# axiom_beta_sensor_cmv12000_v0_13.net
KiCad netlist of a schematic drawn in EAGLE
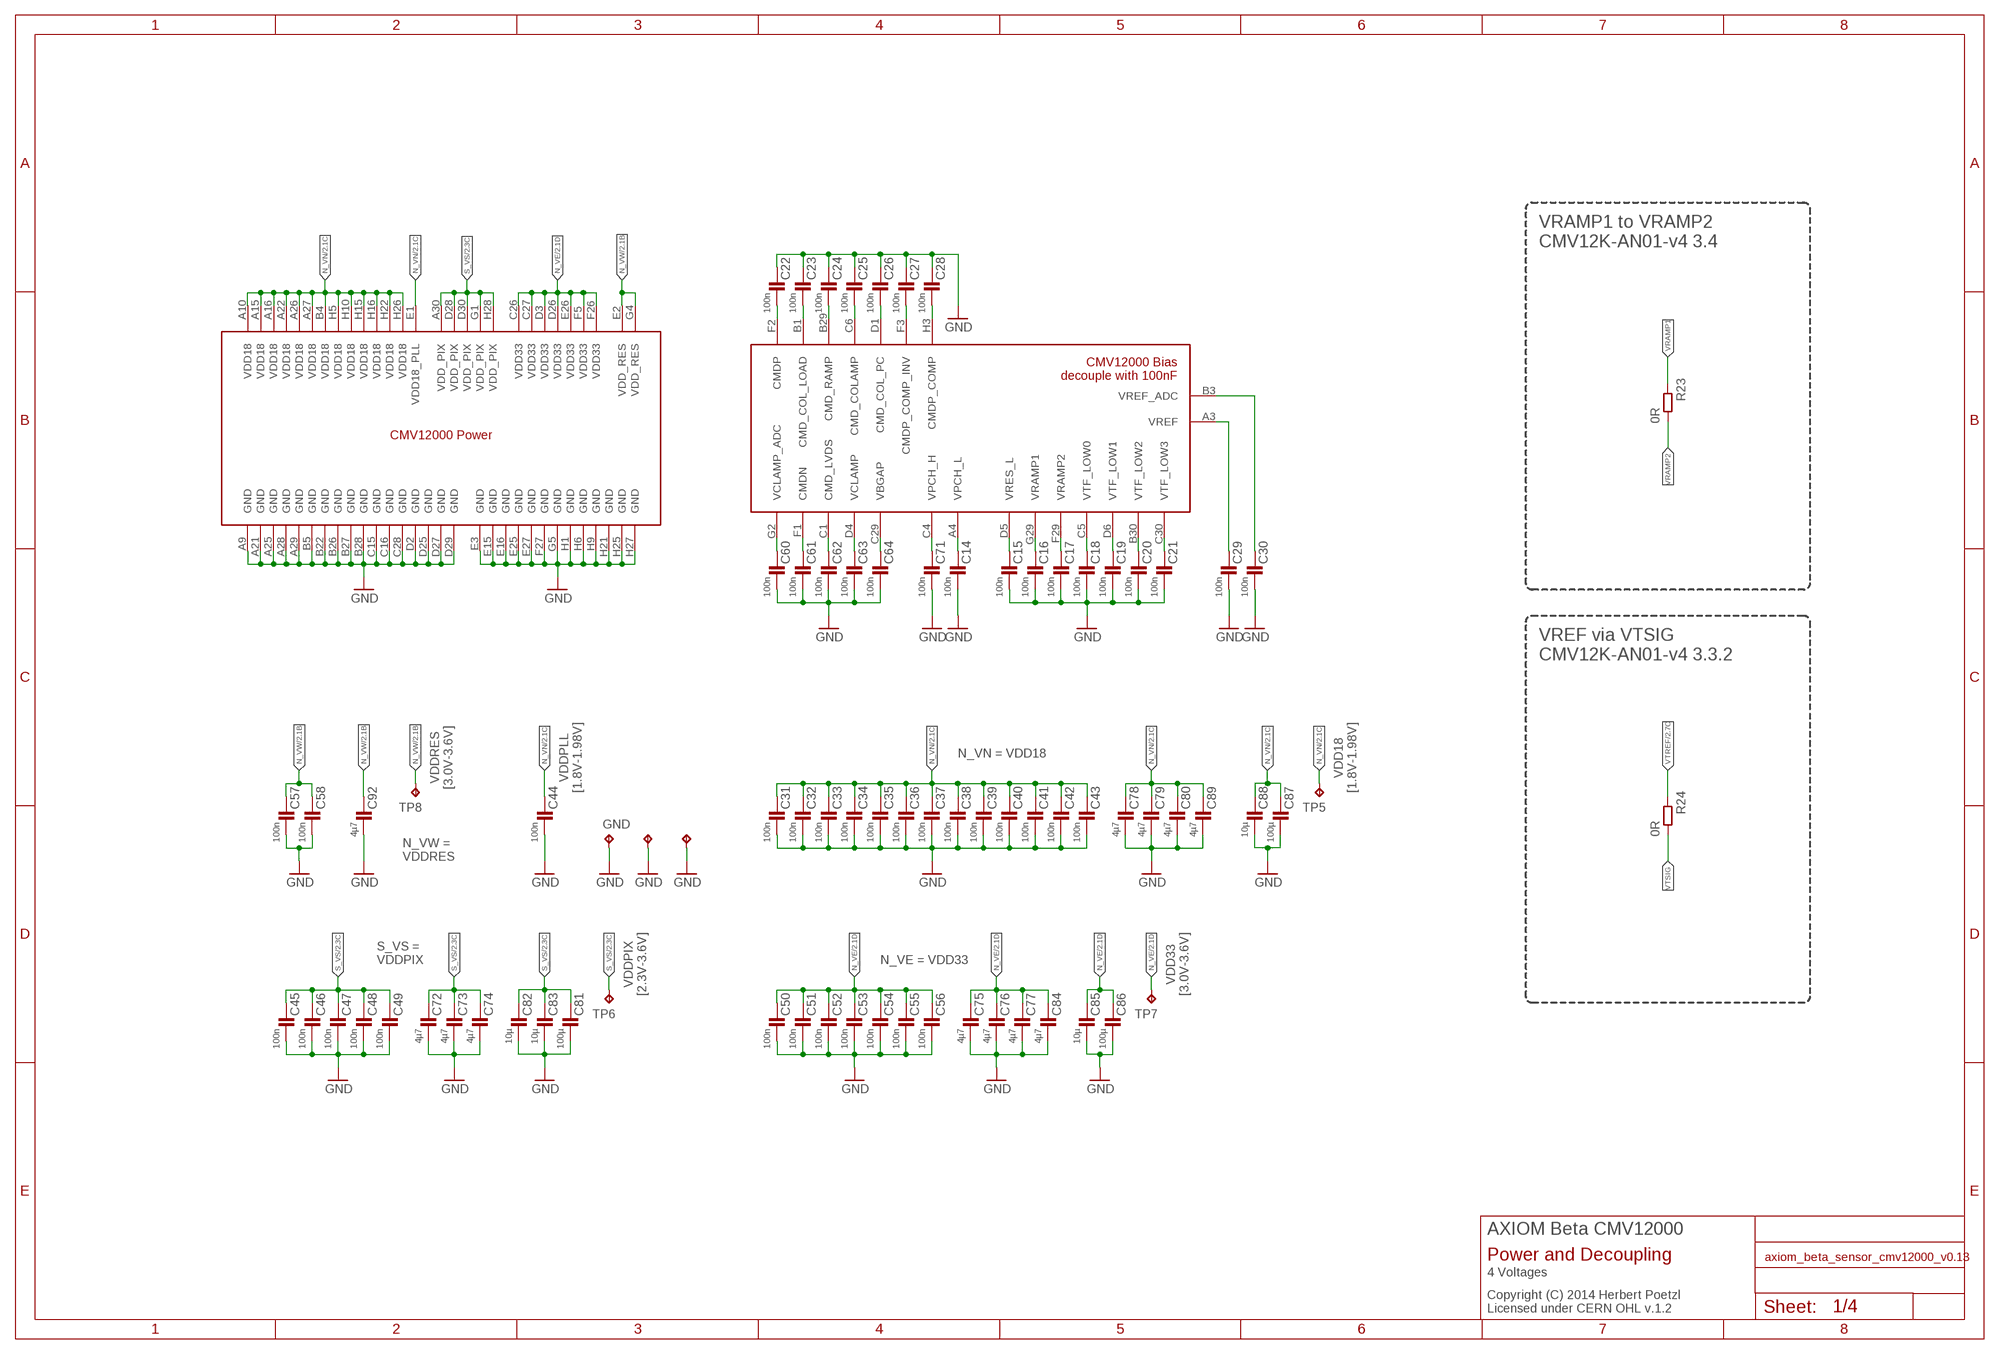
[diagram p0: schematic, sheet 1]
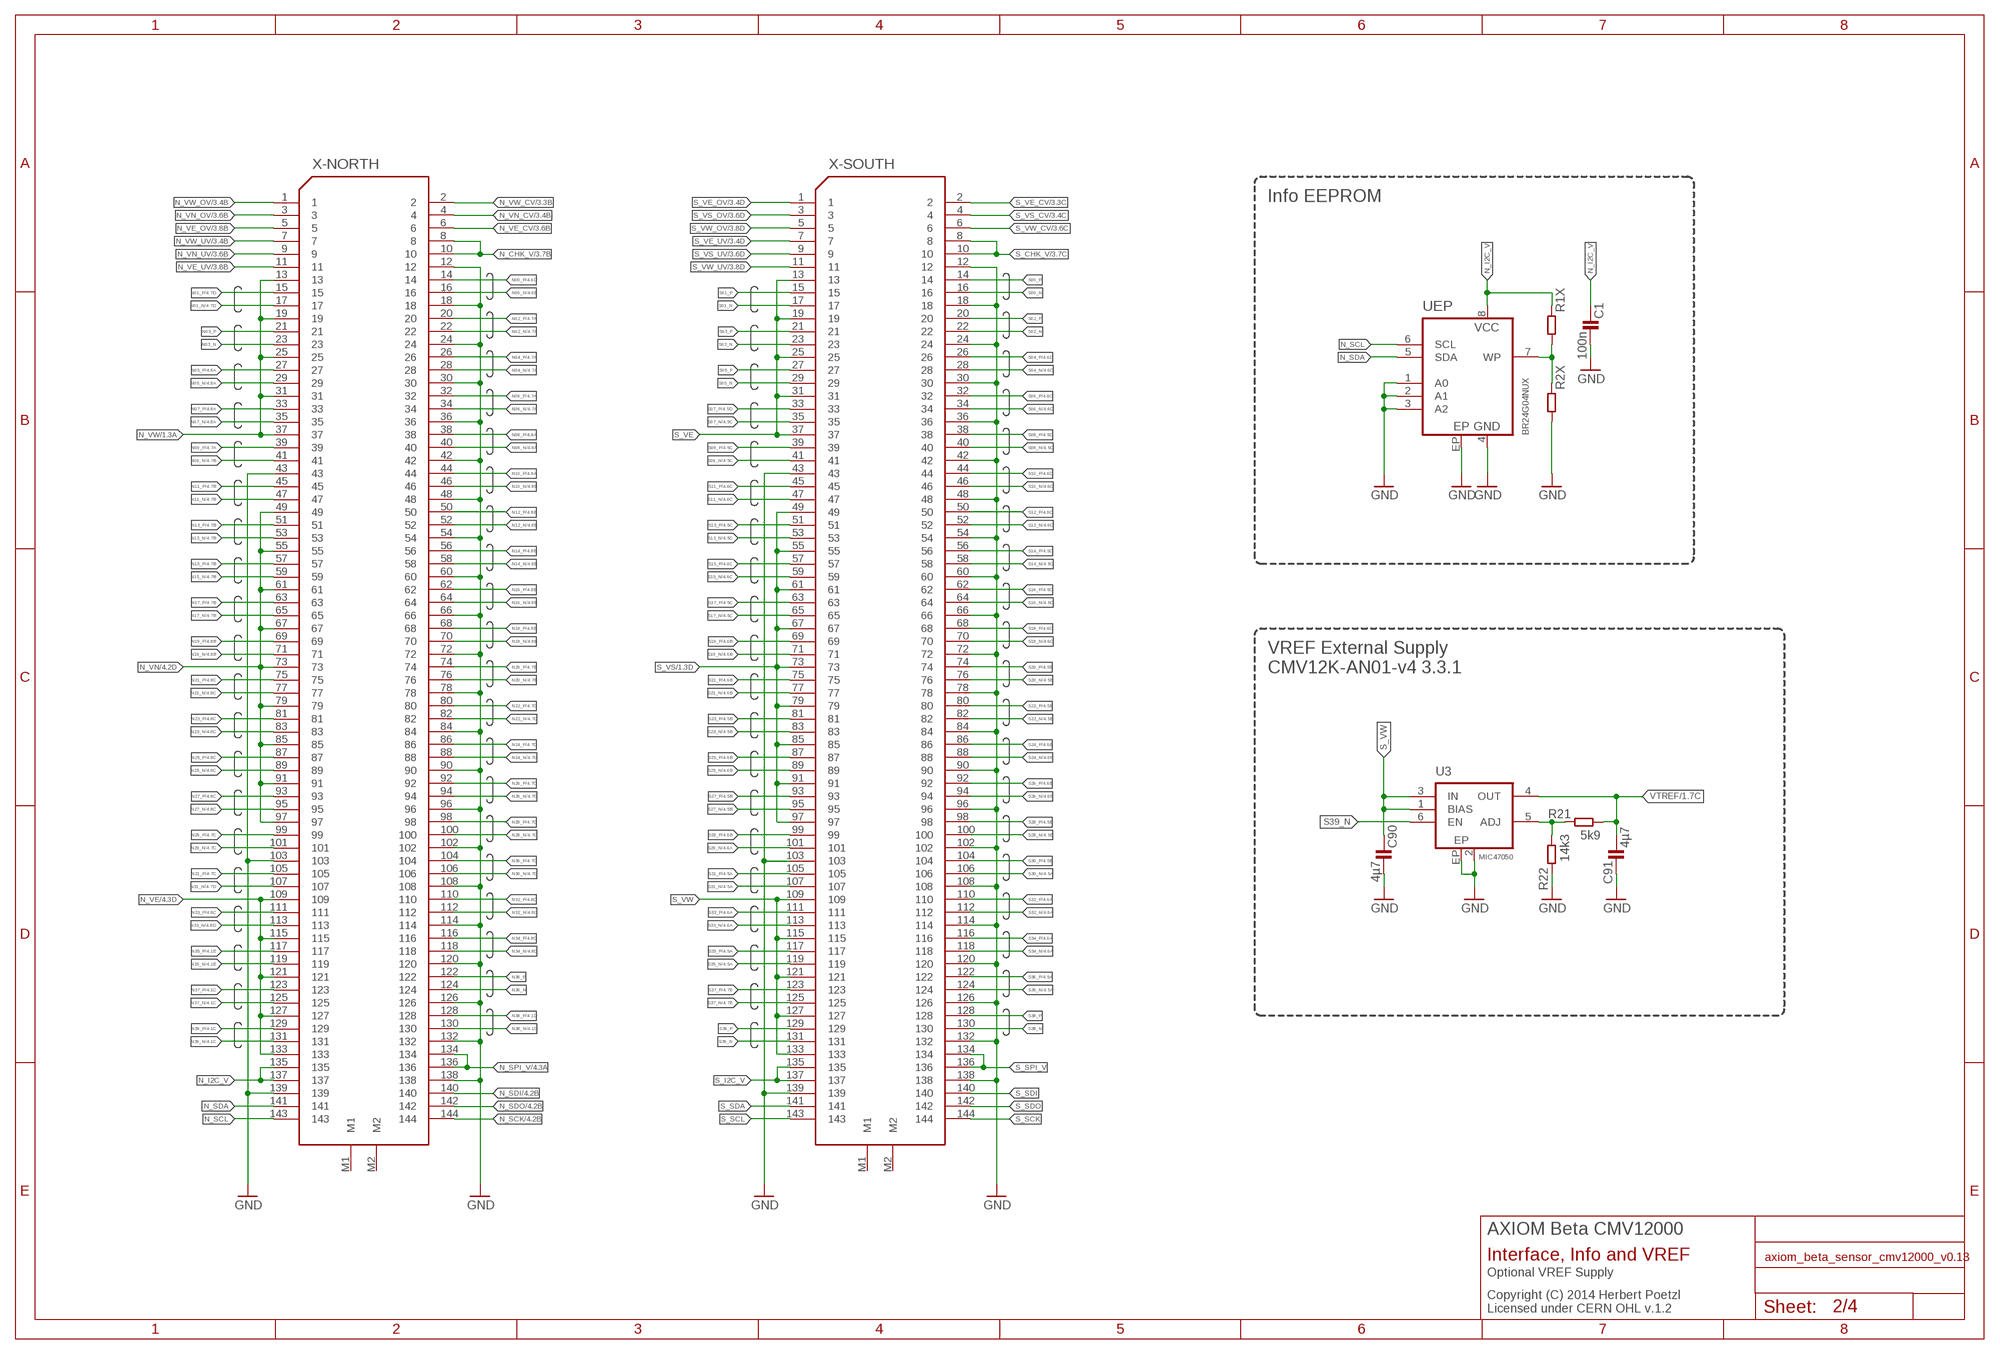
[diagram p1: schematic, sheet 2]
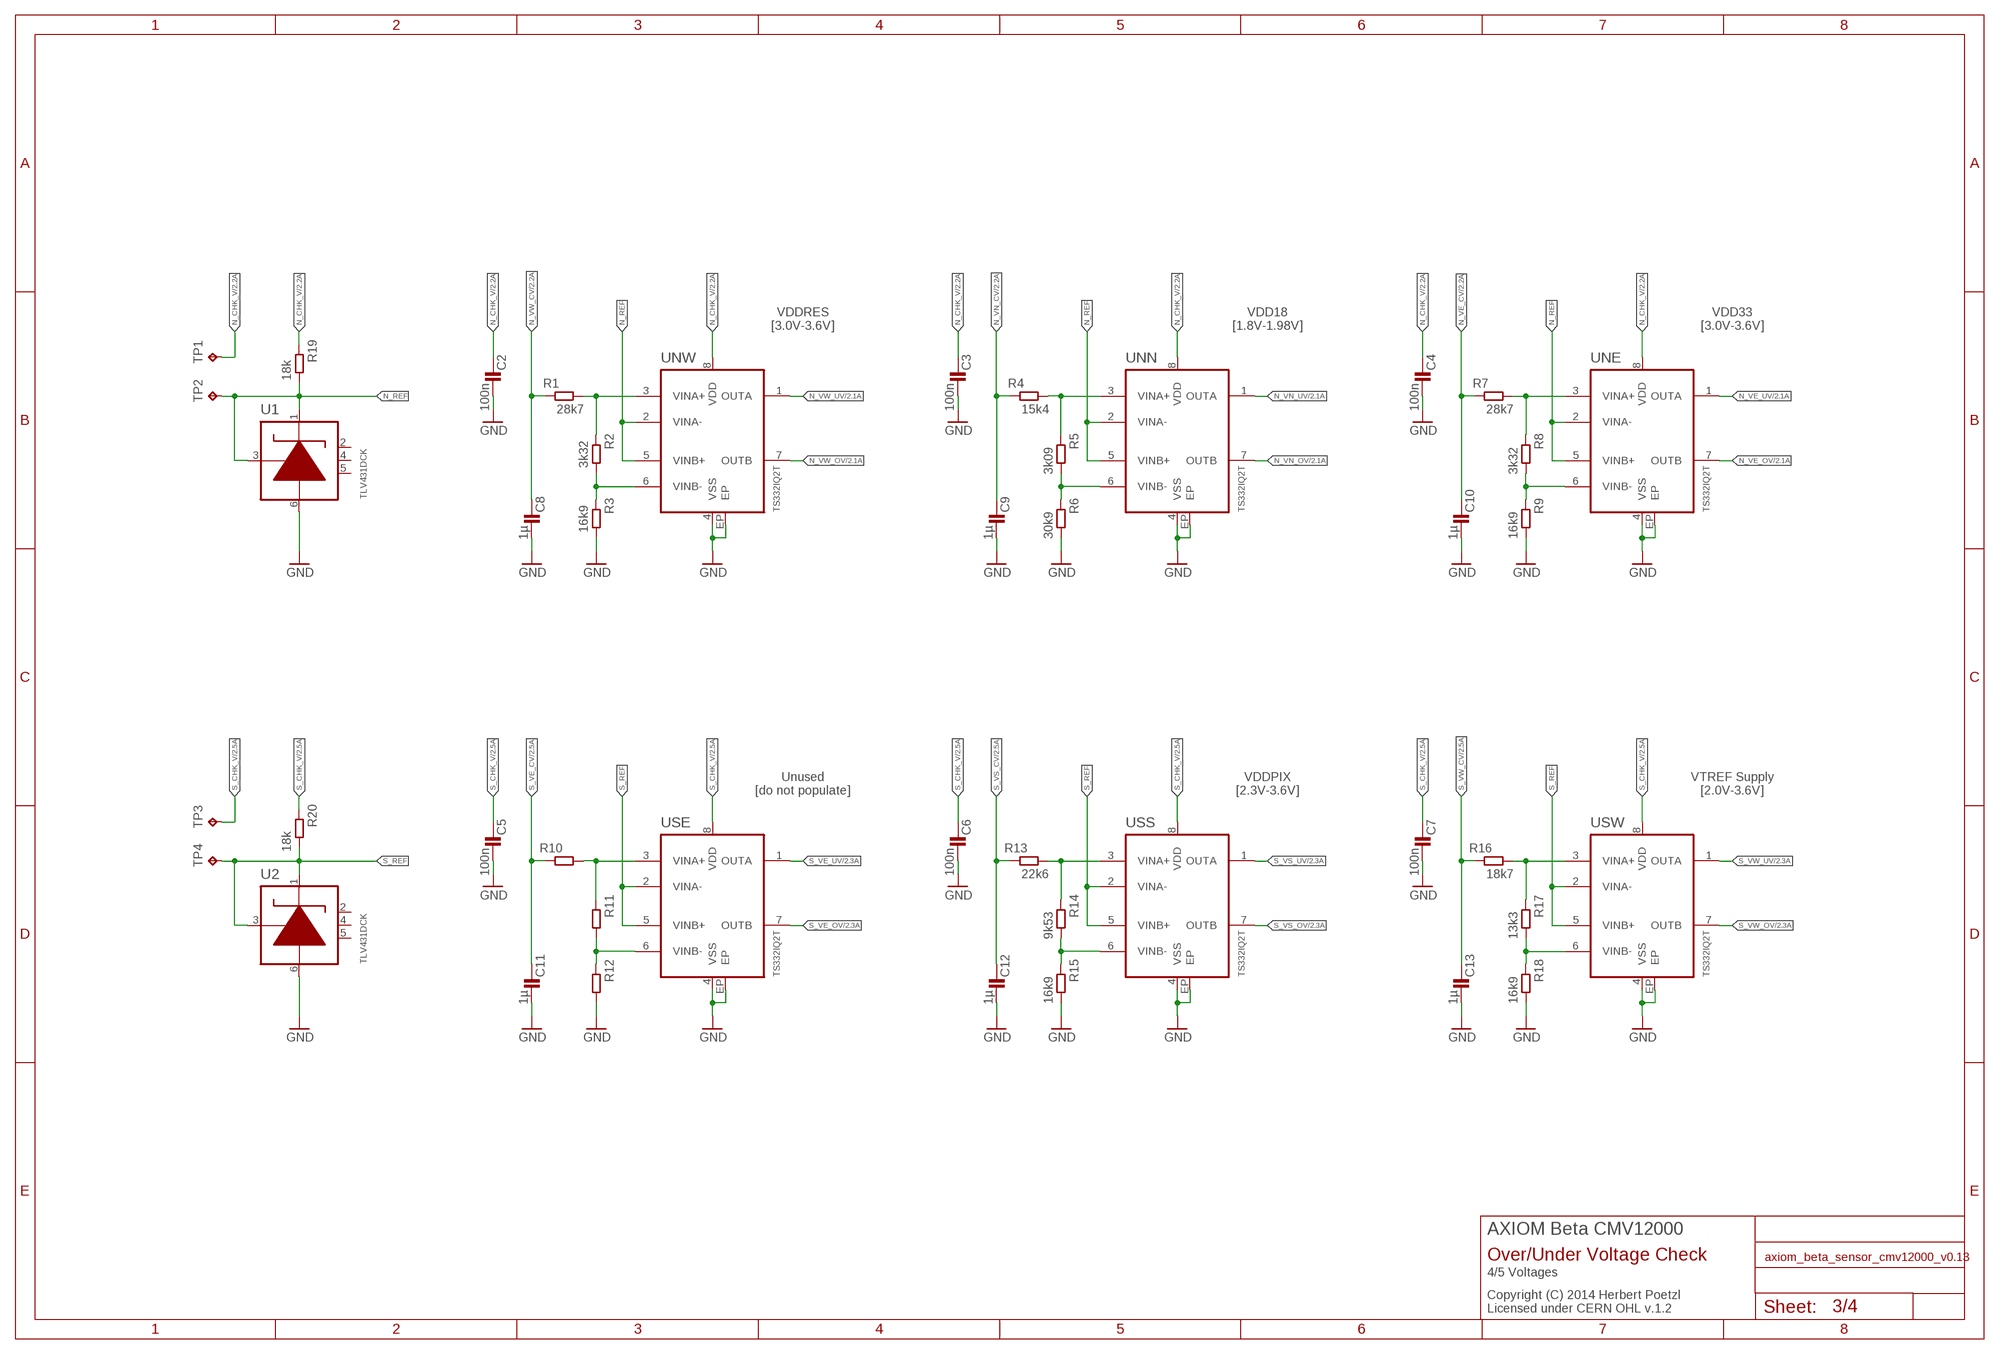
[diagram p2: schematic, sheet 3]
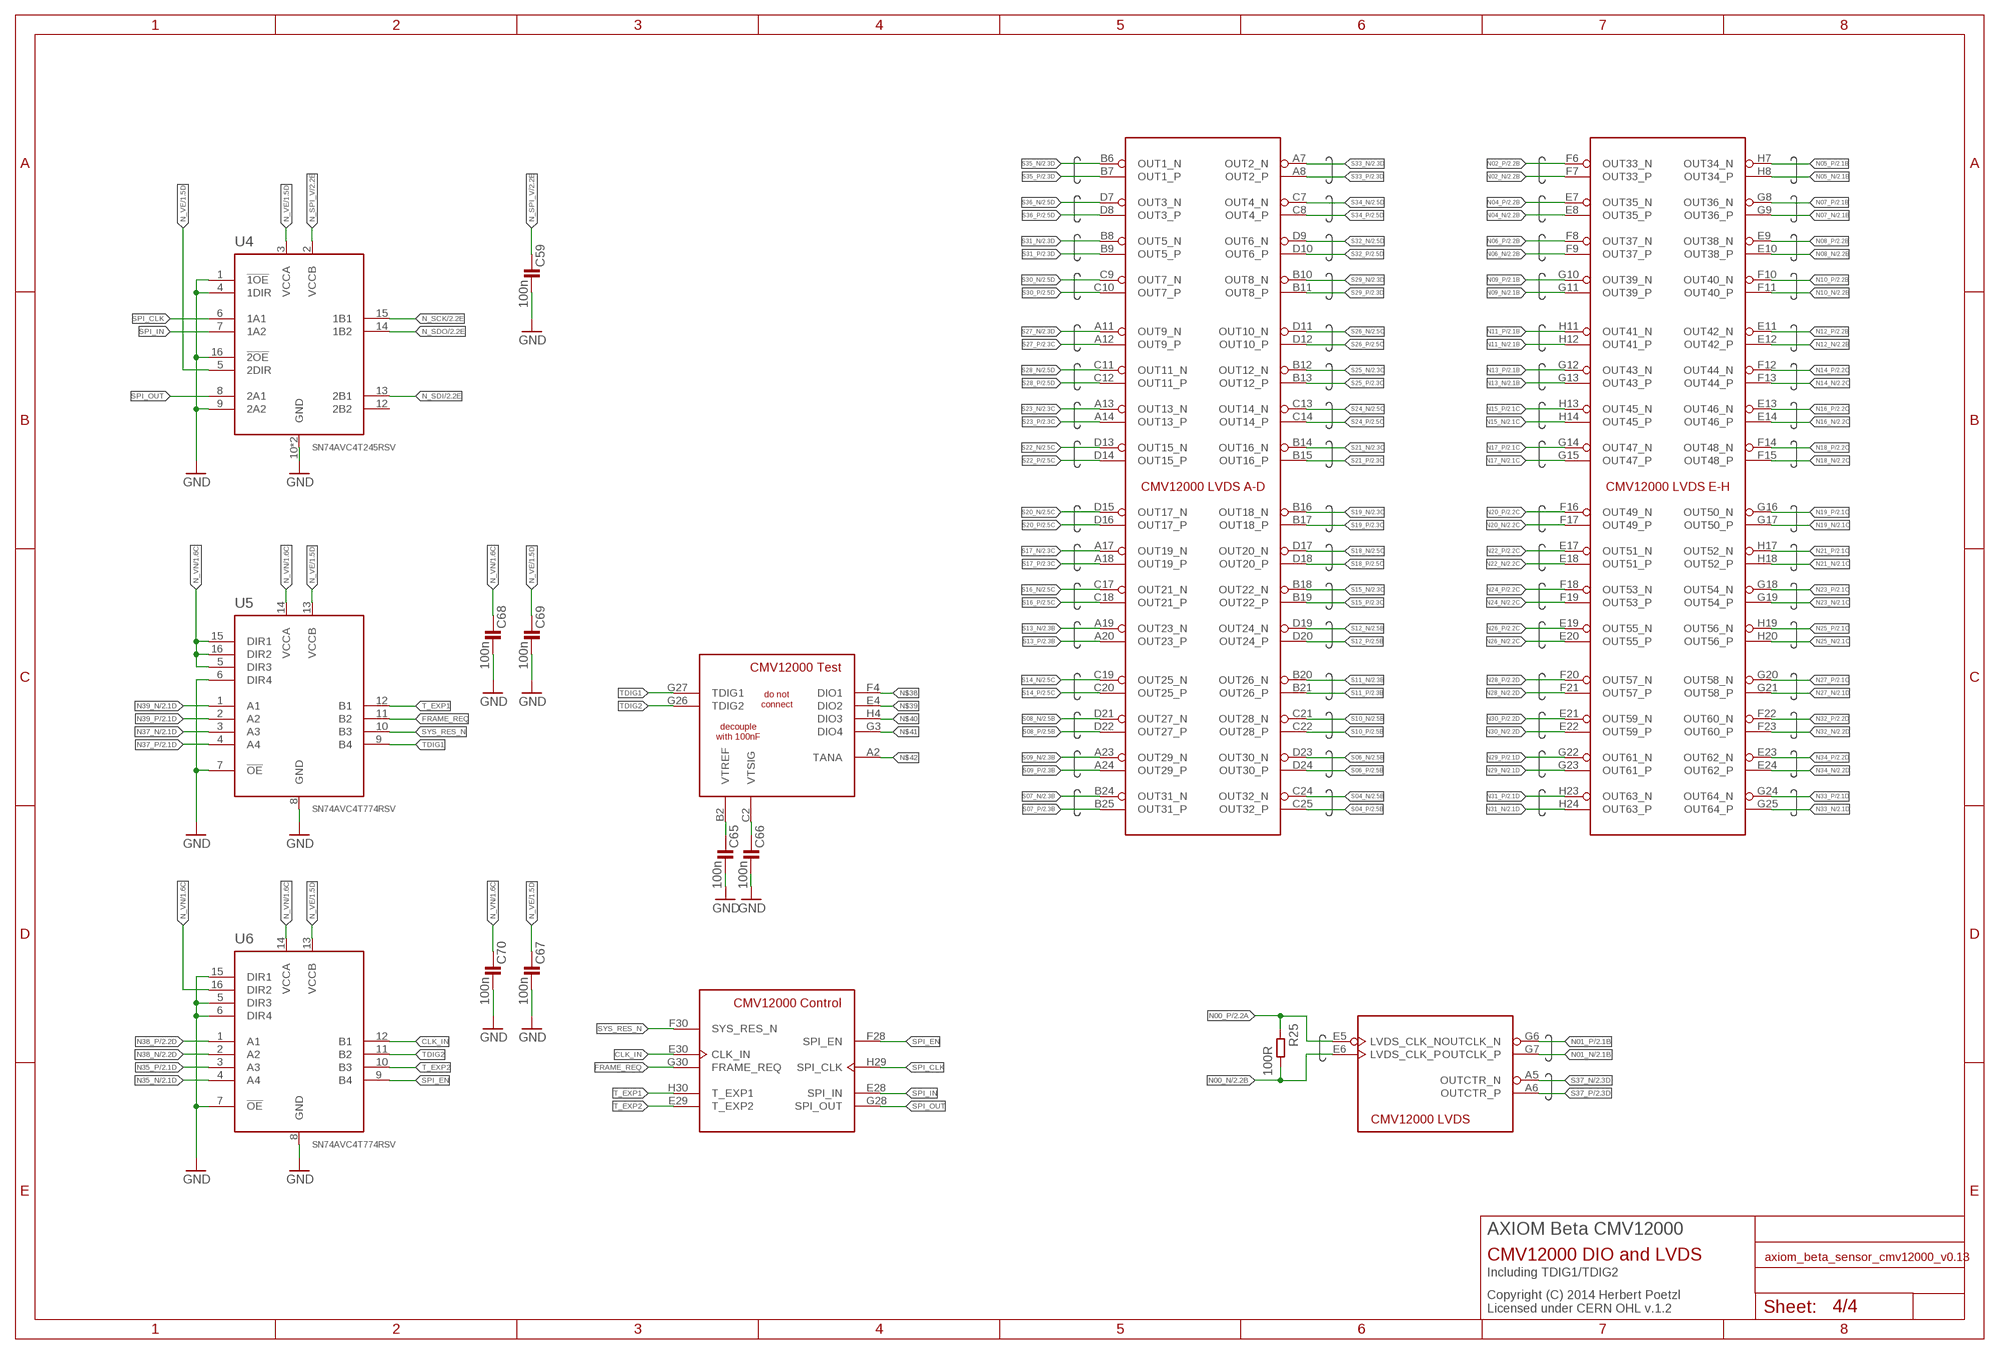
[diagram p3: schematic, sheet 4]

(export (version "E")
  (design (tool "Eeschema 10.0.6"))
  (components
    (comp (ref "C2")
      (value "100n")
      (footprint "eagle-import:0402-C")
      (libsource (lib "eagle-import") (part "C0402-C"))
    )
    (comp (ref "C3")
      (value "100n")
      (footprint "eagle-import:0402-C")
      (libsource (lib "eagle-import") (part "C0402-C"))
    )
    (comp (ref "C4")
      (value "100n")
      (footprint "eagle-import:0402-C")
      (libsource (lib "eagle-import") (part "C0402-C"))
    )
    (comp (ref "C5")
      (value "100n")
      (footprint "eagle-import:0402-C")
      (libsource (lib "eagle-import") (part "C0402-C"))
    )
    (comp (ref "C6")
      (value "100n")
      (footprint "eagle-import:0402-C")
      (libsource (lib "eagle-import") (part "C0402-C"))
    )
    (comp (ref "C7")
      (value "100n")
      (footprint "eagle-import:0402-C")
      (libsource (lib "eagle-import") (part "C0402-C"))
    )
    (comp (ref "C8")
      (value "1µ")
      (footprint "eagle-import:0402-C")
      (libsource (lib "eagle-import") (part "C0402-C"))
    )
    (comp (ref "C9")
      (value "1µ")
      (footprint "eagle-import:0402-C")
      (libsource (lib "eagle-import") (part "C0402-C"))
    )
    (comp (ref "C10")
      (value "1µ")
      (footprint "eagle-import:0402-C")
      (libsource (lib "eagle-import") (part "C0402-C"))
    )
    (comp (ref "C11")
      (value "1µ")
      (footprint "eagle-import:0402-C")
      (libsource (lib "eagle-import") (part "C0402-C"))
    )
    (comp (ref "C12")
      (value "1µ")
      (footprint "eagle-import:0402-C")
      (libsource (lib "eagle-import") (part "C0402-C"))
    )
    (comp (ref "C13")
      (value "1µ")
      (footprint "eagle-import:0402-C")
      (libsource (lib "eagle-import") (part "C0402-C"))
    )
    (comp (ref "R1")
      (value "28k7")
      (footprint "eagle-import:0402-C")
      (libsource (lib "eagle-import") (part "R0402-C"))
    )
    (comp (ref "R2")
      (value "3k32")
      (footprint "eagle-import:0402-C")
      (libsource (lib "eagle-import") (part "R0402-C"))
    )
    (comp (ref "R3")
      (value "16k9")
      (footprint "eagle-import:0402-C")
      (libsource (lib "eagle-import") (part "R0402-C"))
    )
    (comp (ref "R4")
      (value "15k4")
      (footprint "eagle-import:0402-C")
      (libsource (lib "eagle-import") (part "R0402-C"))
    )
    (comp (ref "R5")
      (value "3k09")
      (footprint "eagle-import:0402-C")
      (libsource (lib "eagle-import") (part "R0402-C"))
    )
    (comp (ref "R6")
      (value "30k9")
      (footprint "eagle-import:0402-C")
      (libsource (lib "eagle-import") (part "R0402-C"))
    )
    (comp (ref "R7")
      (value "28k7")
      (footprint "eagle-import:0402-C")
      (libsource (lib "eagle-import") (part "R0402-C"))
    )
    (comp (ref "R8")
      (value "3k32")
      (footprint "eagle-import:0402-C")
      (libsource (lib "eagle-import") (part "R0402-C"))
    )
    (comp (ref "R9")
      (value "16k9")
      (footprint "eagle-import:0402-C")
      (libsource (lib "eagle-import") (part "R0402-C"))
    )
    (comp (ref "R10")
      (value "R0402-C")
      (footprint "eagle-import:0402-C")
      (libsource (lib "eagle-import") (part "R0402-C"))
    )
    (comp (ref "R11")
      (value "R0402-C")
      (footprint "eagle-import:0402-C")
      (libsource (lib "eagle-import") (part "R0402-C"))
    )
    (comp (ref "R12")
      (value "R0402-C")
      (footprint "eagle-import:0402-C")
      (libsource (lib "eagle-import") (part "R0402-C"))
    )
    (comp (ref "R13")
      (value "22k6")
      (footprint "eagle-import:0402-C")
      (libsource (lib "eagle-import") (part "R0402-C"))
    )
    (comp (ref "R14")
      (value "9k53")
      (footprint "eagle-import:0402-C")
      (libsource (lib "eagle-import") (part "R0402-C"))
    )
    (comp (ref "R15")
      (value "16k9")
      (footprint "eagle-import:0402-C")
      (libsource (lib "eagle-import") (part "R0402-C"))
    )
    (comp (ref "R16")
      (value "18k7")
      (footprint "eagle-import:0402-C")
      (libsource (lib "eagle-import") (part "R0402-C"))
    )
    (comp (ref "R17")
      (value "13k3")
      (footprint "eagle-import:0402-C")
      (libsource (lib "eagle-import") (part "R0402-C"))
    )
    (comp (ref "R18")
      (value "16k9")
      (footprint "eagle-import:0402-C")
      (libsource (lib "eagle-import") (part "R0402-C"))
    )
    (comp (ref "R19")
      (value "18k")
      (footprint "eagle-import:0402-C")
      (libsource (lib "eagle-import") (part "R0402-C"))
    )
    (comp (ref "R20")
      (value "18k")
      (footprint "eagle-import:0402-C")
      (libsource (lib "eagle-import") (part "R0402-C"))
    )
    (comp (ref "TP1")
      (value "TPTP10R")
      (footprint "eagle-import:TP10R")
      (libsource (lib "eagle-import") (part "TPTP10R"))
    )
    (comp (ref "TP2")
      (value "TPTP10R")
      (footprint "eagle-import:TP10R")
      (libsource (lib "eagle-import") (part "TPTP10R"))
    )
    (comp (ref "TP3")
      (value "TPTP10R")
      (footprint "eagle-import:TP10R")
      (libsource (lib "eagle-import") (part "TPTP10R"))
    )
    (comp (ref "TP4")
      (value "TPTP10R")
      (footprint "eagle-import:TP10R")
      (libsource (lib "eagle-import") (part "TPTP10R"))
    )
    (comp (ref "U1")
      (value "TLV431DCK")
      (footprint "eagle-import:SOT65P210X110-6N")
      (libsource (lib "eagle-import") (part "TLV431DCK"))
    )
    (comp (ref "U2")
      (value "TLV431DCK")
      (footprint "eagle-import:SOT65P210X110-6N")
      (libsource (lib "eagle-import") (part "TLV431DCK"))
    )
    (comp (ref "UNE")
      (value "TS332IQ2T")
      (footprint "eagle-import:DFN200X200X100-9N")
      (libsource (lib "eagle-import") (part "TS332IQ2T"))
    )
    (comp (ref "UNN")
      (value "TS332IQ2T")
      (footprint "eagle-import:DFN200X200X100-9N")
      (libsource (lib "eagle-import") (part "TS332IQ2T"))
    )
    (comp (ref "UNW")
      (value "TS332IQ2T")
      (footprint "eagle-import:DFN200X200X100-9N")
      (libsource (lib "eagle-import") (part "TS332IQ2T"))
    )
    (comp (ref "USE")
      (value "TS332IQ2T")
      (footprint "eagle-import:DFN200X200X100-9N")
      (libsource (lib "eagle-import") (part "TS332IQ2T"))
    )
    (comp (ref "USS")
      (value "TS332IQ2T")
      (footprint "eagle-import:DFN200X200X100-9N")
      (libsource (lib "eagle-import") (part "TS332IQ2T"))
    )
    (comp (ref "USW")
      (value "TS332IQ2T")
      (footprint "eagle-import:DFN200X200X100-9N")
      (libsource (lib "eagle-import") (part "TS332IQ2T"))
    )
    (comp (ref "C1")
      (value "100n")
      (footprint "eagle-import:0402-C")
      (libsource (lib "eagle-import") (part "C0402-C"))
    )
    (comp (ref "C90")
      (value "4µ7")
      (footprint "eagle-import:0402-C")
      (libsource (lib "eagle-import") (part "C0402-C"))
    )
    (comp (ref "C91")
      (value "4µ7")
      (footprint "eagle-import:0402-C")
      (libsource (lib "eagle-import") (part "C0402-C"))
    )
    (comp (ref "R1X")
      (value "R0402-C")
      (footprint "eagle-import:0402-C")
      (libsource (lib "eagle-import") (part "R0402-C"))
    )
    (comp (ref "R2X")
      (value "R0402-C")
      (footprint "eagle-import:0402-C")
      (libsource (lib "eagle-import") (part "R0402-C"))
    )
    (comp (ref "R21")
      (value "5k9")
      (footprint "eagle-import:0402-C")
      (libsource (lib "eagle-import") (part "R0402-C"))
    )
    (comp (ref "R22")
      (value "14k3")
      (footprint "eagle-import:0402-C")
      (libsource (lib "eagle-import") (part "R0402-C"))
    )
    (comp (ref "U3")
      (value "MIC47050")
      (footprint "eagle-import:MLF-6")
      (libsource (lib "eagle-import") (part "MIC47050-ADJ"))
    )
    (comp (ref "UEP")
      (value "BR24G04NUX")
      (footprint "eagle-import:DFN200X300X100-9N")
      (libsource (lib "eagle-import") (part "BR24G04NUX"))
    )
    (comp (ref "X-NORTH")
      (value "FX10-144P")
      (footprint "eagle-import:FX10A-144P")
      (libsource (lib "eagle-import") (part "FX10-144P"))
    )
    (comp (ref "X-SOUTH")
      (value "FX10-144P")
      (footprint "eagle-import:FX10A-144P")
      (libsource (lib "eagle-import") (part "FX10-144P"))
    )
    (comp (ref "C14")
      (value "100n")
      (footprint "eagle-import:0402-C")
      (libsource (lib "eagle-import") (part "C0402-C"))
    )
    (comp (ref "C15")
      (value "100n")
      (footprint "eagle-import:0402-C")
      (libsource (lib "eagle-import") (part "C0402-C"))
    )
    (comp (ref "C16")
      (value "100n")
      (footprint "eagle-import:0402-C")
      (libsource (lib "eagle-import") (part "C0402-C"))
    )
    (comp (ref "C17")
      (value "100n")
      (footprint "eagle-import:0402-C")
      (libsource (lib "eagle-import") (part "C0402-C"))
    )
    (comp (ref "C18")
      (value "100n")
      (footprint "eagle-import:0402-C")
      (libsource (lib "eagle-import") (part "C0402-C"))
    )
    (comp (ref "C19")
      (value "100n")
      (footprint "eagle-import:0402-C")
      (libsource (lib "eagle-import") (part "C0402-C"))
    )
    (comp (ref "C20")
      (value "100n")
      (footprint "eagle-import:0402-C")
      (libsource (lib "eagle-import") (part "C0402-C"))
    )
    (comp (ref "C21")
      (value "100n")
      (footprint "eagle-import:0402-C")
      (libsource (lib "eagle-import") (part "C0402-C"))
    )
    (comp (ref "C22")
      (value "100n")
      (footprint "eagle-import:0402-C")
      (libsource (lib "eagle-import") (part "C0402-C"))
    )
    (comp (ref "C23")
      (value "100n")
      (footprint "eagle-import:0402-C")
      (libsource (lib "eagle-import") (part "C0402-C"))
    )
    (comp (ref "C24")
      (value "100n")
      (footprint "eagle-import:0402-C")
      (libsource (lib "eagle-import") (part "C0402-C"))
    )
    (comp (ref "C25")
      (value "100n")
      (footprint "eagle-import:0402-C")
      (libsource (lib "eagle-import") (part "C0402-C"))
    )
    (comp (ref "C26")
      (value "100n")
      (footprint "eagle-import:0402-C")
      (libsource (lib "eagle-import") (part "C0402-C"))
    )
    (comp (ref "C27")
      (value "100n")
      (footprint "eagle-import:0402-C")
      (libsource (lib "eagle-import") (part "C0402-C"))
    )
    (comp (ref "C28")
      (value "100n")
      (footprint "eagle-import:0402-C")
      (libsource (lib "eagle-import") (part "C0402-C"))
    )
    (comp (ref "C29")
      (value "100n")
      (footprint "eagle-import:0402-C")
      (libsource (lib "eagle-import") (part "C0402-C"))
    )
    (comp (ref "C30")
      (value "100n")
      (footprint "eagle-import:0402-C")
      (libsource (lib "eagle-import") (part "C0402-C"))
    )
    (comp (ref "C31")
      (value "100n")
      (footprint "eagle-import:0402-C")
      (libsource (lib "eagle-import") (part "C0402-C"))
    )
    (comp (ref "C32")
      (value "100n")
      (footprint "eagle-import:0402-C")
      (libsource (lib "eagle-import") (part "C0402-C"))
    )
    (comp (ref "C33")
      (value "100n")
      (footprint "eagle-import:0402-C")
      (libsource (lib "eagle-import") (part "C0402-C"))
    )
    (comp (ref "C34")
      (value "100n")
      (footprint "eagle-import:0402-C")
      (libsource (lib "eagle-import") (part "C0402-C"))
    )
    (comp (ref "C35")
      (value "100n")
      (footprint "eagle-import:0402-C")
      (libsource (lib "eagle-import") (part "C0402-C"))
    )
    (comp (ref "C36")
      (value "100n")
      (footprint "eagle-import:0402-C")
      (libsource (lib "eagle-import") (part "C0402-C"))
    )
    (comp (ref "C37")
      (value "100n")
      (footprint "eagle-import:0402-C")
      (libsource (lib "eagle-import") (part "C0402-C"))
    )
    (comp (ref "C38")
      (value "100n")
      (footprint "eagle-import:0402-C")
      (libsource (lib "eagle-import") (part "C0402-C"))
    )
    (comp (ref "C39")
      (value "100n")
      (footprint "eagle-import:0402-C")
      (libsource (lib "eagle-import") (part "C0402-C"))
    )
    (comp (ref "C40")
      (value "100n")
      (footprint "eagle-import:0402-C")
      (libsource (lib "eagle-import") (part "C0402-C"))
    )
    (comp (ref "C41")
      (value "100n")
      (footprint "eagle-import:0402-C")
      (libsource (lib "eagle-import") (part "C0402-C"))
    )
    (comp (ref "C42")
      (value "100n")
      (footprint "eagle-import:0402-C")
      (libsource (lib "eagle-import") (part "C0402-C"))
    )
    (comp (ref "C43")
      (value "100n")
      (footprint "eagle-import:0402-C")
      (libsource (lib "eagle-import") (part "C0402-C"))
    )
    (comp (ref "C44")
      (value "100n")
      (footprint "eagle-import:0402-C")
      (libsource (lib "eagle-import") (part "C0402-C"))
    )
    (comp (ref "C45")
      (value "100n")
      (footprint "eagle-import:0402-C")
      (libsource (lib "eagle-import") (part "C0402-C"))
    )
    (comp (ref "C46")
      (value "100n")
      (footprint "eagle-import:0402-C")
      (libsource (lib "eagle-import") (part "C0402-C"))
    )
    (comp (ref "C47")
      (value "100n")
      (footprint "eagle-import:0402-C")
      (libsource (lib "eagle-import") (part "C0402-C"))
    )
    (comp (ref "C48")
      (value "100n")
      (footprint "eagle-import:0402-C")
      (libsource (lib "eagle-import") (part "C0402-C"))
    )
    (comp (ref "C49")
      (value "100n")
      (footprint "eagle-import:0402-C")
      (libsource (lib "eagle-import") (part "C0402-C"))
    )
    (comp (ref "C50")
      (value "100n")
      (footprint "eagle-import:0402-C")
      (libsource (lib "eagle-import") (part "C0402-C"))
    )
    (comp (ref "C51")
      (value "100n")
      (footprint "eagle-import:0402-C")
      (libsource (lib "eagle-import") (part "C0402-C"))
    )
    (comp (ref "C52")
      (value "100n")
      (footprint "eagle-import:0402-C")
      (libsource (lib "eagle-import") (part "C0402-C"))
    )
    (comp (ref "C53")
      (value "100n")
      (footprint "eagle-import:0402-C")
      (libsource (lib "eagle-import") (part "C0402-C"))
    )
    (comp (ref "C54")
      (value "100n")
      (footprint "eagle-import:0402-C")
      (libsource (lib "eagle-import") (part "C0402-C"))
    )
    (comp (ref "C55")
      (value "100n")
      (footprint "eagle-import:0402-C")
      (libsource (lib "eagle-import") (part "C0402-C"))
    )
    (comp (ref "C56")
      (value "100n")
      (footprint "eagle-import:0402-C")
      (libsource (lib "eagle-import") (part "C0402-C"))
    )
    (comp (ref "C57")
      (value "100n")
      (footprint "eagle-import:0402-C")
      (libsource (lib "eagle-import") (part "C0402-C"))
    )
    (comp (ref "C58")
      (value "100n")
      (footprint "eagle-import:0402-C")
      (libsource (lib "eagle-import") (part "C0402-C"))
    )
    (comp (ref "C60")
      (value "100n")
      (footprint "eagle-import:0402-C")
      (libsource (lib "eagle-import") (part "C0402-C"))
    )
    (comp (ref "C61")
      (value "100n")
      (footprint "eagle-import:0402-C")
      (libsource (lib "eagle-import") (part "C0402-C"))
    )
    (comp (ref "C62")
      (value "100n")
      (footprint "eagle-import:0402-C")
      (libsource (lib "eagle-import") (part "C0402-C"))
    )
    (comp (ref "C63")
      (value "100n")
      (footprint "eagle-import:0402-C")
      (libsource (lib "eagle-import") (part "C0402-C"))
    )
    (comp (ref "C64")
      (value "100n")
      (footprint "eagle-import:0402-C")
      (libsource (lib "eagle-import") (part "C0402-C"))
    )
    (comp (ref "C71")
      (value "100n")
      (footprint "eagle-import:0402-C")
      (libsource (lib "eagle-import") (part "C0402-C"))
    )
    (comp (ref "C72")
      (value "4µ7")
      (footprint "eagle-import:0402-B")
      (libsource (lib "eagle-import") (part "C0402-B"))
    )
    (comp (ref "C73")
      (value "4µ7")
      (footprint "eagle-import:0402-C")
      (libsource (lib "eagle-import") (part "C0402-C"))
    )
    (comp (ref "C74")
      (value "4µ7")
      (footprint "eagle-import:0402-C")
      (libsource (lib "eagle-import") (part "C0402-C"))
    )
    (comp (ref "C75")
      (value "4µ7")
      (footprint "eagle-import:0402-C")
      (libsource (lib "eagle-import") (part "C0402-C"))
    )
    (comp (ref "C76")
      (value "4µ7")
      (footprint "eagle-import:0402-C")
      (libsource (lib "eagle-import") (part "C0402-C"))
    )
    (comp (ref "C77")
      (value "4µ7")
      (footprint "eagle-import:0402-B")
      (libsource (lib "eagle-import") (part "C0402-B"))
    )
    (comp (ref "C78")
      (value "4µ7")
      (footprint "eagle-import:0402-B")
      (libsource (lib "eagle-import") (part "C0402-B"))
    )
    (comp (ref "C79")
      (value "4µ7")
      (footprint "eagle-import:0402-C")
      (libsource (lib "eagle-import") (part "C0402-C"))
    )
    (comp (ref "C80")
      (value "4µ7")
      (footprint "eagle-import:0402-C")
      (libsource (lib "eagle-import") (part "C0402-C"))
    )
    (comp (ref "C81")
      (value "100µ")
      (footprint "eagle-import:1206-B")
      (libsource (lib "eagle-import") (part "C1206-B"))
    )
    (comp (ref "C82")
      (value "10µ")
      (footprint "eagle-import:0603-C")
      (libsource (lib "eagle-import") (part "C0603-C"))
    )
    (comp (ref "C83")
      (value "10µ")
      (footprint "eagle-import:0603-C")
      (libsource (lib "eagle-import") (part "C0603-C"))
    )
    (comp (ref "C84")
      (value "4µ7")
      (footprint "eagle-import:0402-C")
      (libsource (lib "eagle-import") (part "C0402-C"))
    )
    (comp (ref "C85")
      (value "10µ")
      (footprint "eagle-import:0603-C")
      (libsource (lib "eagle-import") (part "C0603-C"))
    )
    (comp (ref "C86")
      (value "100µ")
      (footprint "eagle-import:1206-B")
      (libsource (lib "eagle-import") (part "C1206-B"))
    )
    (comp (ref "C87")
      (value "100µ")
      (footprint "eagle-import:1206-B")
      (libsource (lib "eagle-import") (part "C1206-B"))
    )
    (comp (ref "C88")
      (value "10µ")
      (footprint "eagle-import:0603-C")
      (libsource (lib "eagle-import") (part "C0603-C"))
    )
    (comp (ref "C89")
      (value "4µ7")
      (footprint "eagle-import:0402-C")
      (libsource (lib "eagle-import") (part "C0402-C"))
    )
    (comp (ref "C92")
      (value "4µ7")
      (footprint "eagle-import:0402-C")
      (libsource (lib "eagle-import") (part "C0402-C"))
    )
    (comp (ref "GND")
      (value "TPTP10R")
      (footprint "eagle-import:TP10R")
      (libsource (lib "eagle-import") (part "TPTP10R"))
    )
    (comp (ref "GND75")
      (value "TPTP10R")
      (footprint "eagle-import:TP10R")
      (libsource (lib "eagle-import") (part "TPTP10R"))
    )
    (comp (ref "GND77")
      (value "TPTP10R")
      (footprint "eagle-import:TP10R")
      (libsource (lib "eagle-import") (part "TPTP10R"))
    )
    (comp (ref "R23")
      (value "0R")
      (footprint "eagle-import:0402-C")
      (libsource (lib "eagle-import") (part "R0402-C"))
    )
    (comp (ref "R24")
      (value "0R")
      (footprint "eagle-import:0402-C")
      (libsource (lib "eagle-import") (part "R0402-C"))
    )
    (comp (ref "SENSOR")
      (value "CMV12000ANDON")
      (footprint "eagle-import:10-30-07-237-400T4")
      (libsource (lib "eagle-import") (part "CMV12000ANDON"))
    )
    (comp (ref "TP5")
      (value "TPTP10R")
      (footprint "eagle-import:TP10R")
      (libsource (lib "eagle-import") (part "TPTP10R"))
    )
    (comp (ref "TP6")
      (value "TPTP10R")
      (footprint "eagle-import:TP10R")
      (libsource (lib "eagle-import") (part "TPTP10R"))
    )
    (comp (ref "TP7")
      (value "TPTP10R")
      (footprint "eagle-import:TP10R")
      (libsource (lib "eagle-import") (part "TPTP10R"))
    )
    (comp (ref "TP8")
      (value "TPTP10R")
      (footprint "eagle-import:TP10R")
      (libsource (lib "eagle-import") (part "TPTP10R"))
    )
    (comp (ref "C59")
      (value "100n")
      (footprint "eagle-import:0402-C")
      (libsource (lib "eagle-import") (part "C0402-C"))
    )
    (comp (ref "C65")
      (value "100n")
      (footprint "eagle-import:0402-C")
      (libsource (lib "eagle-import") (part "C0402-C"))
    )
    (comp (ref "C66")
      (value "100n")
      (footprint "eagle-import:0402-C")
      (libsource (lib "eagle-import") (part "C0402-C"))
    )
    (comp (ref "C67")
      (value "100n")
      (footprint "eagle-import:0402-C")
      (libsource (lib "eagle-import") (part "C0402-C"))
    )
    (comp (ref "C68")
      (value "100n")
      (footprint "eagle-import:0402-C")
      (libsource (lib "eagle-import") (part "C0402-C"))
    )
    (comp (ref "C69")
      (value "100n")
      (footprint "eagle-import:0402-C")
      (libsource (lib "eagle-import") (part "C0402-C"))
    )
    (comp (ref "C70")
      (value "100n")
      (footprint "eagle-import:0402-C")
      (libsource (lib "eagle-import") (part "C0402-C"))
    )
    (comp (ref "R25")
      (value "100R")
      (footprint "eagle-import:0402-C")
      (libsource (lib "eagle-import") (part "R0402-C"))
    )
    (comp (ref "U4")
      (value "SN74AVC4T245RSV")
      (footprint "eagle-import:QFN40P185X265X55-16N")
      (libsource (lib "eagle-import") (part "SN74AVC4T245RSV"))
    )
    (comp (ref "U5")
      (value "SN74AVC4T774RSV")
      (footprint "eagle-import:QFN40P185X265X55-16N")
      (libsource (lib "eagle-import") (part "SN74AVC4T774RSV"))
    )
    (comp (ref "U6")
      (value "SN74AVC4T774RSV")
      (footprint "eagle-import:QFN40P185X265X55-16N")
      (libsource (lib "eagle-import") (part "SN74AVC4T774RSV"))
    )
  )
  (nets
    (net (code "1") (name "CLK_IN") (class "Default")
      (node (ref "SENSOR") (pin "E30") (pinfunction "CLK_IN_E30") (pintype "input"))
      (node (ref "U6") (pin "12") (pinfunction "B1_12") (pintype "bidirectional"))
    )
    (net (code "2") (name "FRAME_REQ") (class "Default")
      (node (ref "SENSOR") (pin "G30") (pinfunction "FRAME_REQ_G30") (pintype "input"))
      (node (ref "U5") (pin "11") (pinfunction "B2_11") (pintype "bidirectional"))
    )
    (net (code "3") (name "GND") (class "Default")
      (node (ref "C1") (pin "2") (pinfunction "2_2") (pintype "passive"))
      (node (ref "C10") (pin "2") (pinfunction "2_2") (pintype "passive"))
      (node (ref "C11") (pin "2") (pinfunction "2_2") (pintype "passive"))
      (node (ref "C12") (pin "2") (pinfunction "2_2") (pintype "passive"))
      (node (ref "C13") (pin "2") (pinfunction "2_2") (pintype "passive"))
      (node (ref "C14") (pin "2") (pinfunction "2_2") (pintype "passive"))
      (node (ref "C15") (pin "2") (pinfunction "2_2") (pintype "passive"))
      (node (ref "C16") (pin "2") (pinfunction "2_2") (pintype "passive"))
      (node (ref "C17") (pin "2") (pinfunction "2_2") (pintype "passive"))
      (node (ref "C18") (pin "2") (pinfunction "2_2") (pintype "passive"))
      (node (ref "C19") (pin "2") (pinfunction "2_2") (pintype "passive"))
      (node (ref "C2") (pin "2") (pinfunction "2_2") (pintype "passive"))
      (node (ref "C20") (pin "2") (pinfunction "2_2") (pintype "passive"))
      (node (ref "C21") (pin "2") (pinfunction "2_2") (pintype "passive"))
      (node (ref "C22") (pin "1") (pinfunction "1_1") (pintype "passive"))
      (node (ref "C23") (pin "1") (pinfunction "1_1") (pintype "passive"))
      (node (ref "C24") (pin "1") (pinfunction "1_1") (pintype "passive"))
      (node (ref "C25") (pin "1") (pinfunction "1_1") (pintype "passive"))
      (node (ref "C26") (pin "1") (pinfunction "1_1") (pintype "passive"))
      (node (ref "C27") (pin "1") (pinfunction "1_1") (pintype "passive"))
      (node (ref "C28") (pin "1") (pinfunction "1_1") (pintype "passive"))
      (node (ref "C29") (pin "2") (pinfunction "2_2") (pintype "passive"))
      (node (ref "C3") (pin "2") (pinfunction "2_2") (pintype "passive"))
      (node (ref "C30") (pin "2") (pinfunction "2_2") (pintype "passive"))
      (node (ref "C31") (pin "2") (pinfunction "2_2") (pintype "passive"))
      (node (ref "C32") (pin "2") (pinfunction "2_2") (pintype "passive"))
      (node (ref "C33") (pin "2") (pinfunction "2_2") (pintype "passive"))
      (node (ref "C34") (pin "2") (pinfunction "2_2") (pintype "passive"))
      (node (ref "C35") (pin "2") (pinfunction "2_2") (pintype "passive"))
      (node (ref "C36") (pin "2") (pinfunction "2_2") (pintype "passive"))
      (node (ref "C37") (pin "2") (pinfunction "2_2") (pintype "passive"))
      (node (ref "C38") (pin "2") (pinfunction "2_2") (pintype "passive"))
      (node (ref "C39") (pin "2") (pinfunction "2_2") (pintype "passive"))
      (node (ref "C4") (pin "2") (pinfunction "2_2") (pintype "passive"))
      (node (ref "C40") (pin "2") (pinfunction "2_2") (pintype "passive"))
      (node (ref "C41") (pin "2") (pinfunction "2_2") (pintype "passive"))
      (node (ref "C42") (pin "2") (pinfunction "2_2") (pintype "passive"))
      (node (ref "C43") (pin "2") (pinfunction "2_2") (pintype "passive"))
      (node (ref "C44") (pin "2") (pinfunction "2_2") (pintype "passive"))
      (node (ref "C45") (pin "2") (pinfunction "2_2") (pintype "passive"))
      (node (ref "C46") (pin "2") (pinfunction "2_2") (pintype "passive"))
      (node (ref "C47") (pin "2") (pinfunction "2_2") (pintype "passive"))
      (node (ref "C48") (pin "2") (pinfunction "2_2") (pintype "passive"))
      (node (ref "C49") (pin "2") (pinfunction "2_2") (pintype "passive"))
      (node (ref "C5") (pin "2") (pinfunction "2_2") (pintype "passive"))
      (node (ref "C50") (pin "2") (pinfunction "2_2") (pintype "passive"))
      (node (ref "C51") (pin "2") (pinfunction "2_2") (pintype "passive"))
      (node (ref "C52") (pin "2") (pinfunction "2_2") (pintype "passive"))
      (node (ref "C53") (pin "2") (pinfunction "2_2") (pintype "passive"))
      (node (ref "C54") (pin "2") (pinfunction "2_2") (pintype "passive"))
      (node (ref "C55") (pin "2") (pinfunction "2_2") (pintype "passive"))
      (node (ref "C56") (pin "2") (pinfunction "2_2") (pintype "passive"))
      (node (ref "C57") (pin "2") (pinfunction "2_2") (pintype "passive"))
      (node (ref "C58") (pin "2") (pinfunction "2_2") (pintype "passive"))
      (node (ref "C59") (pin "2") (pinfunction "2_2") (pintype "passive"))
      (node (ref "C6") (pin "2") (pinfunction "2_2") (pintype "passive"))
      (node (ref "C60") (pin "2") (pinfunction "2_2") (pintype "passive"))
      (node (ref "C61") (pin "2") (pinfunction "2_2") (pintype "passive"))
      (node (ref "C62") (pin "2") (pinfunction "2_2") (pintype "passive"))
      (node (ref "C63") (pin "2") (pinfunction "2_2") (pintype "passive"))
      (node (ref "C64") (pin "2") (pinfunction "2_2") (pintype "passive"))
      (node (ref "C65") (pin "2") (pinfunction "2_2") (pintype "passive"))
      (node (ref "C66") (pin "2") (pinfunction "2_2") (pintype "passive"))
      (node (ref "C67") (pin "2") (pinfunction "2_2") (pintype "passive"))
      (node (ref "C68") (pin "2") (pinfunction "2_2") (pintype "passive"))
      (node (ref "C69") (pin "2") (pinfunction "2_2") (pintype "passive"))
      (node (ref "C7") (pin "2") (pinfunction "2_2") (pintype "passive"))
      (node (ref "C70") (pin "2") (pinfunction "2_2") (pintype "passive"))
      (node (ref "C71") (pin "2") (pinfunction "2_2") (pintype "passive"))
      (node (ref "C72") (pin "2") (pinfunction "2_2") (pintype "passive"))
      (node (ref "C73") (pin "2") (pinfunction "2_2") (pintype "passive"))
      (node (ref "C74") (pin "2") (pinfunction "2_2") (pintype "passive"))
      (node (ref "C75") (pin "2") (pinfunction "2_2") (pintype "passive"))
      (node (ref "C76") (pin "2") (pinfunction "2_2") (pintype "passive"))
      (node (ref "C77") (pin "2") (pinfunction "2_2") (pintype "passive"))
      (node (ref "C78") (pin "2") (pinfunction "2_2") (pintype "passive"))
      (node (ref "C79") (pin "2") (pinfunction "2_2") (pintype "passive"))
      (node (ref "C8") (pin "2") (pinfunction "2_2") (pintype "passive"))
      (node (ref "C80") (pin "2") (pinfunction "2_2") (pintype "passive"))
      (node (ref "C81") (pin "2") (pinfunction "2_2") (pintype "passive"))
      (node (ref "C82") (pin "2") (pinfunction "2_2") (pintype "passive"))
      (node (ref "C83") (pin "2") (pinfunction "2_2") (pintype "passive"))
      (node (ref "C84") (pin "2") (pinfunction "2_2") (pintype "passive"))
      (node (ref "C85") (pin "2") (pinfunction "2_2") (pintype "passive"))
      (node (ref "C86") (pin "2") (pinfunction "2_2") (pintype "passive"))
      (node (ref "C87") (pin "2") (pinfunction "2_2") (pintype "passive"))
      (node (ref "C88") (pin "2") (pinfunction "2_2") (pintype "passive"))
      (node (ref "C89") (pin "2") (pinfunction "2_2") (pintype "passive"))
      (node (ref "C9") (pin "2") (pinfunction "2_2") (pintype "passive"))
      (node (ref "C90") (pin "2") (pinfunction "2_2") (pintype "passive"))
      (node (ref "C91") (pin "1") (pinfunction "1_1") (pintype "passive"))
      (node (ref "C92") (pin "2") (pinfunction "2_2") (pintype "passive"))
      (node (ref "GND") (pin "TP") (pinfunction "TP_TP") (pintype "input"))
      (node (ref "GND75") (pin "TP") (pinfunction "TP_TP") (pintype "input"))
      (node (ref "GND77") (pin "TP") (pinfunction "TP_TP") (pintype "input"))
      (node (ref "R12") (pin "2") (pinfunction "2_2") (pintype "passive"))
      (node (ref "R15") (pin "2") (pinfunction "2_2") (pintype "passive"))
      (node (ref "R18") (pin "2") (pinfunction "2_2") (pintype "passive"))
      (node (ref "R22") (pin "1") (pinfunction "1_1") (pintype "passive"))
      (node (ref "R2X") (pin "2") (pinfunction "2_2") (pintype "passive"))
      (node (ref "R3") (pin "2") (pinfunction "2_2") (pintype "passive"))
      (node (ref "R6") (pin "2") (pinfunction "2_2") (pintype "passive"))
      (node (ref "R9") (pin "2") (pinfunction "2_2") (pintype "passive"))
      (node (ref "SENSOR") (pin "A21") (pinfunction "GND_A21") (pintype "power_in"))
      (node (ref "SENSOR") (pin "A25") (pinfunction "GND_A25") (pintype "power_in"))
      (node (ref "SENSOR") (pin "A28") (pinfunction "GND_A28") (pintype "power_in"))
      (node (ref "SENSOR") (pin "A29") (pinfunction "GND_A29") (pintype "power_in"))
      (node (ref "SENSOR") (pin "A9") (pinfunction "GND_A9") (pintype "power_in"))
      (node (ref "SENSOR") (pin "B22") (pinfunction "GND_B22") (pintype "power_in"))
      (node (ref "SENSOR") (pin "B26") (pinfunction "GND_B26") (pintype "power_in"))
      (node (ref "SENSOR") (pin "B27") (pinfunction "GND_B27") (pintype "power_in"))
      (node (ref "SENSOR") (pin "B28") (pinfunction "GND_B28") (pintype "power_in"))
      (node (ref "SENSOR") (pin "B5") (pinfunction "GND_B5") (pintype "power_in"))
      (node (ref "SENSOR") (pin "C15") (pinfunction "GND_C15") (pintype "power_in"))
      (node (ref "SENSOR") (pin "C16") (pinfunction "GND_C16") (pintype "power_in"))
      (node (ref "SENSOR") (pin "C28") (pinfunction "GND_C28") (pintype "power_in"))
      (node (ref "SENSOR") (pin "D2") (pinfunction "GND_D2") (pintype "power_in"))
      (node (ref "SENSOR") (pin "D25") (pinfunction "GND_D25") (pintype "power_in"))
      (node (ref "SENSOR") (pin "D27") (pinfunction "GND_D27") (pintype "power_in"))
      (node (ref "SENSOR") (pin "D29") (pinfunction "GND_D29") (pintype "power_in"))
      (node (ref "SENSOR") (pin "E15") (pinfunction "GND_E15") (pintype "power_in"))
      (node (ref "SENSOR") (pin "E16") (pinfunction "GND_E16") (pintype "power_in"))
      (node (ref "SENSOR") (pin "E25") (pinfunction "GND_E25") (pintype "power_in"))
      (node (ref "SENSOR") (pin "E27") (pinfunction "GND_E27") (pintype "power_in"))
      (node (ref "SENSOR") (pin "E3") (pinfunction "GND_E3") (pintype "power_in"))
      (node (ref "SENSOR") (pin "F27") (pinfunction "GND_F27") (pintype "power_in"))
      (node (ref "SENSOR") (pin "G5") (pinfunction "GND_G5") (pintype "power_in"))
      (node (ref "SENSOR") (pin "H1") (pinfunction "GND_H1") (pintype "power_in"))
      (node (ref "SENSOR") (pin "H21") (pinfunction "GND_H21") (pintype "power_in"))
      (node (ref "SENSOR") (pin "H25") (pinfunction "GND_H25") (pintype "power_in"))
      (node (ref "SENSOR") (pin "H27") (pinfunction "GND_H27") (pintype "power_in"))
      (node (ref "SENSOR") (pin "H6") (pinfunction "GND_H6") (pintype "power_in"))
      (node (ref "SENSOR") (pin "H9") (pinfunction "GND_H9") (pintype "power_in"))
      (node (ref "U1") (pin "6") (pinfunction "ANODE_6") (pintype "input"))
      (node (ref "U2") (pin "6") (pinfunction "ANODE_6") (pintype "input"))
      (node (ref "U3") (pin "2") (pinfunction "GND_2") (pintype "power_in"))
      (node (ref "U3") (pin "EP") (pinfunction "EP_EP") (pintype "power_in"))
      (node (ref "U4") (pin "1") (pinfunction "~{1OE}_1") (pintype "input"))
      (node (ref "U4") (pin "10") (pinfunction "GND_10") (pintype "passive"))
      (node (ref "U4") (pin "11") (pinfunction "GND_11") (pintype "passive"))
      (node (ref "U4") (pin "16") (pinfunction "~{2OE}_16") (pintype "input"))
      (node (ref "U4") (pin "4") (pinfunction "1DIR_4") (pintype "input"))
      (node (ref "U4") (pin "9") (pinfunction "2A2_9") (pintype "output"))
      (node (ref "U5") (pin "6") (pinfunction "DIR4_6") (pintype "input"))
      (node (ref "U5") (pin "7") (pinfunction "~{OE}_7") (pintype "input"))
      (node (ref "U5") (pin "8") (pinfunction "GND_8") (pintype "passive"))
      (node (ref "U6") (pin "15") (pinfunction "DIR1_15") (pintype "input"))
      (node (ref "U6") (pin "5") (pinfunction "DIR3_5") (pintype "input"))
      (node (ref "U6") (pin "6") (pinfunction "DIR4_6") (pintype "input"))
      (node (ref "U6") (pin "7") (pinfunction "~{OE}_7") (pintype "input"))
      (node (ref "U6") (pin "8") (pinfunction "GND_8") (pintype "passive"))
      (node (ref "UEP") (pin "1") (pinfunction "A0_1") (pintype "input"))
      (node (ref "UEP") (pin "2") (pinfunction "A1_2") (pintype "input"))
      (node (ref "UEP") (pin "3") (pinfunction "A2_3") (pintype "input"))
      (node (ref "UEP") (pin "4") (pinfunction "GND_4") (pintype "passive"))
      (node (ref "UEP") (pin "EP") (pinfunction "EP_EP") (pintype "passive"))
      (node (ref "UNE") (pin "4") (pinfunction "VSS_4") (pintype "power_in"))
      (node (ref "UNE") (pin "EP") (pinfunction "EP_EP") (pintype "passive"))
      (node (ref "UNN") (pin "4") (pinfunction "VSS_4") (pintype "power_in"))
      (node (ref "UNN") (pin "EP") (pinfunction "EP_EP") (pintype "passive"))
      (node (ref "UNW") (pin "4") (pinfunction "VSS_4") (pintype "power_in"))
      (node (ref "UNW") (pin "EP") (pinfunction "EP_EP") (pintype "passive"))
      (node (ref "USE") (pin "4") (pinfunction "VSS_4") (pintype "power_in"))
      (node (ref "USE") (pin "EP") (pinfunction "EP_EP") (pintype "passive"))
      (node (ref "USS") (pin "4") (pinfunction "VSS_4") (pintype "power_in"))
      (node (ref "USS") (pin "EP") (pinfunction "EP_EP") (pintype "passive"))
      (node (ref "USW") (pin "4") (pinfunction "VSS_4") (pintype "power_in"))
      (node (ref "USW") (pin "EP") (pinfunction "EP_EP") (pintype "passive"))
      (node (ref "X-NORTH") (pin "102") (pinfunction "102_102") (pintype "bidirectional"))
      (node (ref "X-NORTH") (pin "103") (pinfunction "103_103") (pintype "bidirectional"))
      (node (ref "X-NORTH") (pin "108") (pinfunction "108_108") (pintype "bidirectional"))
      (node (ref "X-NORTH") (pin "114") (pinfunction "114_114") (pintype "bidirectional"))
      (node (ref "X-NORTH") (pin "12") (pinfunction "12_12") (pintype "bidirectional"))
      (node (ref "X-NORTH") (pin "120") (pinfunction "120_120") (pintype "bidirectional"))
      (node (ref "X-NORTH") (pin "126") (pinfunction "126_126") (pintype "bidirectional"))
      (node (ref "X-NORTH") (pin "132") (pinfunction "132_132") (pintype "bidirectional"))
      (node (ref "X-NORTH") (pin "138") (pinfunction "138_138") (pintype "bidirectional"))
      (node (ref "X-NORTH") (pin "139") (pinfunction "139_139") (pintype "bidirectional"))
      (node (ref "X-NORTH") (pin "18") (pinfunction "18_18") (pintype "bidirectional"))
      (node (ref "X-NORTH") (pin "24") (pinfunction "24_24") (pintype "bidirectional"))
      (node (ref "X-NORTH") (pin "30") (pinfunction "30_30") (pintype "bidirectional"))
      (node (ref "X-NORTH") (pin "36") (pinfunction "36_36") (pintype "bidirectional"))
      (node (ref "X-NORTH") (pin "42") (pinfunction "42_42") (pintype "bidirectional"))
      (node (ref "X-NORTH") (pin "43") (pinfunction "43_43") (pintype "bidirectional"))
      (node (ref "X-NORTH") (pin "48") (pinfunction "48_48") (pintype "bidirectional"))
      (node (ref "X-NORTH") (pin "54") (pinfunction "54_54") (pintype "bidirectional"))
      (node (ref "X-NORTH") (pin "60") (pinfunction "60_60") (pintype "bidirectional"))
      (node (ref "X-NORTH") (pin "66") (pinfunction "66_66") (pintype "bidirectional"))
      (node (ref "X-NORTH") (pin "72") (pinfunction "72_72") (pintype "bidirectional"))
      (node (ref "X-NORTH") (pin "78") (pinfunction "78_78") (pintype "bidirectional"))
      (node (ref "X-NORTH") (pin "84") (pinfunction "84_84") (pintype "bidirectional"))
      (node (ref "X-NORTH") (pin "90") (pinfunction "90_90") (pintype "bidirectional"))
      (node (ref "X-NORTH") (pin "96") (pinfunction "96_96") (pintype "bidirectional"))
      (node (ref "X-SOUTH") (pin "102") (pinfunction "102_102") (pintype "bidirectional"))
      (node (ref "X-SOUTH") (pin "103") (pinfunction "103_103") (pintype "bidirectional"))
      (node (ref "X-SOUTH") (pin "108") (pinfunction "108_108") (pintype "bidirectional"))
      (node (ref "X-SOUTH") (pin "114") (pinfunction "114_114") (pintype "bidirectional"))
      (node (ref "X-SOUTH") (pin "12") (pinfunction "12_12") (pintype "bidirectional"))
      (node (ref "X-SOUTH") (pin "120") (pinfunction "120_120") (pintype "bidirectional"))
      (node (ref "X-SOUTH") (pin "126") (pinfunction "126_126") (pintype "bidirectional"))
      (node (ref "X-SOUTH") (pin "132") (pinfunction "132_132") (pintype "bidirectional"))
      (node (ref "X-SOUTH") (pin "138") (pinfunction "138_138") (pintype "bidirectional"))
      (node (ref "X-SOUTH") (pin "139") (pinfunction "139_139") (pintype "bidirectional"))
      (node (ref "X-SOUTH") (pin "18") (pinfunction "18_18") (pintype "bidirectional"))
      (node (ref "X-SOUTH") (pin "24") (pinfunction "24_24") (pintype "bidirectional"))
      (node (ref "X-SOUTH") (pin "30") (pinfunction "30_30") (pintype "bidirectional"))
      (node (ref "X-SOUTH") (pin "36") (pinfunction "36_36") (pintype "bidirectional"))
      (node (ref "X-SOUTH") (pin "42") (pinfunction "42_42") (pintype "bidirectional"))
      (node (ref "X-SOUTH") (pin "43") (pinfunction "43_43") (pintype "bidirectional"))
      (node (ref "X-SOUTH") (pin "48") (pinfunction "48_48") (pintype "bidirectional"))
      (node (ref "X-SOUTH") (pin "54") (pinfunction "54_54") (pintype "bidirectional"))
      (node (ref "X-SOUTH") (pin "60") (pinfunction "60_60") (pintype "bidirectional"))
      (node (ref "X-SOUTH") (pin "66") (pinfunction "66_66") (pintype "bidirectional"))
      (node (ref "X-SOUTH") (pin "72") (pinfunction "72_72") (pintype "bidirectional"))
      (node (ref "X-SOUTH") (pin "78") (pinfunction "78_78") (pintype "bidirectional"))
      (node (ref "X-SOUTH") (pin "84") (pinfunction "84_84") (pintype "bidirectional"))
      (node (ref "X-SOUTH") (pin "90") (pinfunction "90_90") (pintype "bidirectional"))
      (node (ref "X-SOUTH") (pin "96") (pinfunction "96_96") (pintype "bidirectional"))
    )
    (net (code "4") (name "N$38") (class "Default")
      (node (ref "SENSOR") (pin "F4") (pinfunction "DIO1_F4") (pintype "output"))
    )
    (net (code "5") (name "N$39") (class "Default")
      (node (ref "SENSOR") (pin "E4") (pinfunction "DIO2_E4") (pintype "output"))
    )
    (net (code "6") (name "N$40") (class "Default")
      (node (ref "SENSOR") (pin "H4") (pinfunction "DIO3_H4") (pintype "output"))
    )
    (net (code "7") (name "N$41") (class "Default")
      (node (ref "SENSOR") (pin "G3") (pinfunction "DIO4_G3") (pintype "output"))
    )
    (net (code "8") (name "N$42") (class "Default")
      (node (ref "SENSOR") (pin "A2") (pinfunction "TANA_A2") (pintype "output"))
    )
    (net (code "9") (name "N00_N") (class "Default")
      (node (ref "R25") (pin "2") (pinfunction "2_2") (pintype "passive"))
      (node (ref "SENSOR") (pin "E6") (pinfunction "LVDS_CLK_P_E6") (pintype "input"))
      (node (ref "X-NORTH") (pin "16") (pinfunction "16_16") (pintype "bidirectional"))
    )
    (net (code "10") (name "N00_P") (class "Default")
      (node (ref "R25") (pin "1") (pinfunction "1_1") (pintype "passive"))
      (node (ref "SENSOR") (pin "E5") (pinfunction "LVDS_CLK_N_E5") (pintype "input"))
      (node (ref "X-NORTH") (pin "14") (pinfunction "14_14") (pintype "bidirectional"))
    )
    (net (code "11") (name "N01_N") (class "Default")
      (node (ref "SENSOR") (pin "G7") (pinfunction "OUTCLK_P_G7") (pintype "output"))
      (node (ref "X-NORTH") (pin "17") (pinfunction "17_17") (pintype "bidirectional"))
    )
    (net (code "12") (name "N01_P") (class "Default")
      (node (ref "SENSOR") (pin "G6") (pinfunction "OUTCLK_N_G6") (pintype "output"))
      (node (ref "X-NORTH") (pin "15") (pinfunction "15_15") (pintype "bidirectional"))
    )
    (net (code "13") (name "N02_N") (class "Default")
      (node (ref "SENSOR") (pin "F7") (pinfunction "OUT33_P_F7") (pintype "output"))
      (node (ref "X-NORTH") (pin "22") (pinfunction "22_22") (pintype "bidirectional"))
    )
    (net (code "14") (name "N02_P") (class "Default")
      (node (ref "SENSOR") (pin "F6") (pinfunction "OUT33_N_F6") (pintype "output"))
      (node (ref "X-NORTH") (pin "20") (pinfunction "20_20") (pintype "bidirectional"))
    )
    (net (code "15") (name "N03_N") (class "Default")
      (node (ref "X-NORTH") (pin "23") (pinfunction "23_23") (pintype "bidirectional"))
    )
    (net (code "16") (name "N03_P") (class "Default")
      (node (ref "X-NORTH") (pin "21") (pinfunction "21_21") (pintype "bidirectional"))
    )
    (net (code "17") (name "N04_N") (class "Default")
      (node (ref "SENSOR") (pin "E8") (pinfunction "OUT35_P_E8") (pintype "output"))
      (node (ref "X-NORTH") (pin "28") (pinfunction "28_28") (pintype "bidirectional"))
    )
    (net (code "18") (name "N04_P") (class "Default")
      (node (ref "SENSOR") (pin "E7") (pinfunction "OUT35_N_E7") (pintype "output"))
      (node (ref "X-NORTH") (pin "26") (pinfunction "26_26") (pintype "bidirectional"))
    )
    (net (code "19") (name "N05_N") (class "Default")
      (node (ref "SENSOR") (pin "H8") (pinfunction "OUT34_P_H8") (pintype "output"))
      (node (ref "X-NORTH") (pin "29") (pinfunction "29_29") (pintype "bidirectional"))
    )
    (net (code "20") (name "N05_P") (class "Default")
      (node (ref "SENSOR") (pin "H7") (pinfunction "OUT34_N_H7") (pintype "output"))
      (node (ref "X-NORTH") (pin "27") (pinfunction "27_27") (pintype "bidirectional"))
    )
    (net (code "21") (name "N06_N") (class "Default")
      (node (ref "SENSOR") (pin "F9") (pinfunction "OUT37_P_F9") (pintype "output"))
      (node (ref "X-NORTH") (pin "34") (pinfunction "34_34") (pintype "bidirectional"))
    )
    (net (code "22") (name "N06_P") (class "Default")
      (node (ref "SENSOR") (pin "F8") (pinfunction "OUT37_N_F8") (pintype "output"))
      (node (ref "X-NORTH") (pin "32") (pinfunction "32_32") (pintype "bidirectional"))
    )
    (net (code "23") (name "N07_N") (class "Default")
      (node (ref "SENSOR") (pin "G9") (pinfunction "OUT36_P_G9") (pintype "output"))
      (node (ref "X-NORTH") (pin "35") (pinfunction "35_35") (pintype "bidirectional"))
    )
    (net (code "24") (name "N07_P") (class "Default")
      (node (ref "SENSOR") (pin "G8") (pinfunction "OUT36_N_G8") (pintype "output"))
      (node (ref "X-NORTH") (pin "33") (pinfunction "33_33") (pintype "bidirectional"))
    )
    (net (code "25") (name "N08_N") (class "Default")
      (node (ref "SENSOR") (pin "E10") (pinfunction "OUT38_P_E10") (pintype "output"))
      (node (ref "X-NORTH") (pin "40") (pinfunction "40_40") (pintype "bidirectional"))
    )
    (net (code "26") (name "N08_P") (class "Default")
      (node (ref "SENSOR") (pin "E9") (pinfunction "OUT38_N_E9") (pintype "output"))
      (node (ref "X-NORTH") (pin "38") (pinfunction "38_38") (pintype "bidirectional"))
    )
    (net (code "27") (name "N09_N") (class "Default")
      (node (ref "SENSOR") (pin "G11") (pinfunction "OUT39_P_G11") (pintype "output"))
      (node (ref "X-NORTH") (pin "41") (pinfunction "41_41") (pintype "bidirectional"))
    )
    (net (code "28") (name "N09_P") (class "Default")
      (node (ref "SENSOR") (pin "G10") (pinfunction "OUT39_N_G10") (pintype "output"))
      (node (ref "X-NORTH") (pin "39") (pinfunction "39_39") (pintype "bidirectional"))
    )
    (net (code "29") (name "N10_N") (class "Default")
      (node (ref "SENSOR") (pin "F11") (pinfunction "OUT40_P_F11") (pintype "output"))
      (node (ref "X-NORTH") (pin "46") (pinfunction "46_46") (pintype "bidirectional"))
    )
    (net (code "30") (name "N10_P") (class "Default")
      (node (ref "SENSOR") (pin "F10") (pinfunction "OUT40_N_F10") (pintype "output"))
      (node (ref "X-NORTH") (pin "44") (pinfunction "44_44") (pintype "bidirectional"))
    )
    (net (code "31") (name "N11_N") (class "Default")
      (node (ref "SENSOR") (pin "H12") (pinfunction "OUT41_P_H12") (pintype "output"))
      (node (ref "X-NORTH") (pin "47") (pinfunction "47_47") (pintype "bidirectional"))
    )
    (net (code "32") (name "N11_P") (class "Default")
      (node (ref "SENSOR") (pin "H11") (pinfunction "OUT41_N_H11") (pintype "output"))
      (node (ref "X-NORTH") (pin "45") (pinfunction "45_45") (pintype "bidirectional"))
    )
    (net (code "33") (name "N12_N") (class "Default")
      (node (ref "SENSOR") (pin "E12") (pinfunction "OUT42_P_E12") (pintype "output"))
      (node (ref "X-NORTH") (pin "52") (pinfunction "52_52") (pintype "bidirectional"))
    )
    (net (code "34") (name "N12_P") (class "Default")
      (node (ref "SENSOR") (pin "E11") (pinfunction "OUT42_N_E11") (pintype "output"))
      (node (ref "X-NORTH") (pin "50") (pinfunction "50_50") (pintype "bidirectional"))
    )
    (net (code "35") (name "N13_N") (class "Default")
      (node (ref "SENSOR") (pin "G13") (pinfunction "OUT43_P_G13") (pintype "output"))
      (node (ref "X-NORTH") (pin "53") (pinfunction "53_53") (pintype "bidirectional"))
    )
    (net (code "36") (name "N13_P") (class "Default")
      (node (ref "SENSOR") (pin "G12") (pinfunction "OUT43_N_G12") (pintype "output"))
      (node (ref "X-NORTH") (pin "51") (pinfunction "51_51") (pintype "bidirectional"))
    )
    (net (code "37") (name "N14_N") (class "Default")
      (node (ref "SENSOR") (pin "F13") (pinfunction "OUT44_P_F13") (pintype "output"))
      (node (ref "X-NORTH") (pin "58") (pinfunction "58_58") (pintype "bidirectional"))
    )
    (net (code "38") (name "N14_P") (class "Default")
      (node (ref "SENSOR") (pin "F12") (pinfunction "OUT44_N_F12") (pintype "output"))
      (node (ref "X-NORTH") (pin "56") (pinfunction "56_56") (pintype "bidirectional"))
    )
    (net (code "39") (name "N15_N") (class "Default")
      (node (ref "SENSOR") (pin "H14") (pinfunction "OUT45_P_H14") (pintype "output"))
      (node (ref "X-NORTH") (pin "59") (pinfunction "59_59") (pintype "bidirectional"))
    )
    (net (code "40") (name "N15_P") (class "Default")
      (node (ref "SENSOR") (pin "H13") (pinfunction "OUT45_N_H13") (pintype "output"))
      (node (ref "X-NORTH") (pin "57") (pinfunction "57_57") (pintype "bidirectional"))
    )
    (net (code "41") (name "N16_N") (class "Default")
      (node (ref "SENSOR") (pin "E14") (pinfunction "OUT46_P_E14") (pintype "output"))
      (node (ref "X-NORTH") (pin "64") (pinfunction "64_64") (pintype "bidirectional"))
    )
    (net (code "42") (name "N16_P") (class "Default")
      (node (ref "SENSOR") (pin "E13") (pinfunction "OUT46_N_E13") (pintype "output"))
      (node (ref "X-NORTH") (pin "62") (pinfunction "62_62") (pintype "bidirectional"))
    )
    (net (code "43") (name "N17_N") (class "Default")
      (node (ref "SENSOR") (pin "G15") (pinfunction "OUT47_P_G15") (pintype "output"))
      (node (ref "X-NORTH") (pin "65") (pinfunction "65_65") (pintype "bidirectional"))
    )
    (net (code "44") (name "N17_P") (class "Default")
      (node (ref "SENSOR") (pin "G14") (pinfunction "OUT47_N_G14") (pintype "output"))
      (node (ref "X-NORTH") (pin "63") (pinfunction "63_63") (pintype "bidirectional"))
    )
    (net (code "45") (name "N18_N") (class "Default")
      (node (ref "SENSOR") (pin "F15") (pinfunction "OUT48_P_F15") (pintype "output"))
      (node (ref "X-NORTH") (pin "70") (pinfunction "70_70") (pintype "bidirectional"))
    )
    (net (code "46") (name "N18_P") (class "Default")
      (node (ref "SENSOR") (pin "F14") (pinfunction "OUT48_N_F14") (pintype "output"))
      (node (ref "X-NORTH") (pin "68") (pinfunction "68_68") (pintype "bidirectional"))
    )
    (net (code "47") (name "N19_N") (class "Default")
      (node (ref "SENSOR") (pin "G17") (pinfunction "OUT50_P_G17") (pintype "output"))
      (node (ref "X-NORTH") (pin "71") (pinfunction "71_71") (pintype "bidirectional"))
    )
    (net (code "48") (name "N19_P") (class "Default")
      (node (ref "SENSOR") (pin "G16") (pinfunction "OUT50_N_G16") (pintype "output"))
      (node (ref "X-NORTH") (pin "69") (pinfunction "69_69") (pintype "bidirectional"))
    )
    (net (code "49") (name "N20_N") (class "Default")
      (node (ref "SENSOR") (pin "F17") (pinfunction "OUT49_P_F17") (pintype "output"))
      (node (ref "X-NORTH") (pin "76") (pinfunction "76_76") (pintype "bidirectional"))
    )
    (net (code "50") (name "N20_P") (class "Default")
      (node (ref "SENSOR") (pin "F16") (pinfunction "OUT49_N_F16") (pintype "output"))
      (node (ref "X-NORTH") (pin "74") (pinfunction "74_74") (pintype "bidirectional"))
    )
    (net (code "51") (name "N21_N") (class "Default")
      (node (ref "SENSOR") (pin "H18") (pinfunction "OUT52_P_H18") (pintype "output"))
      (node (ref "X-NORTH") (pin "77") (pinfunction "77_77") (pintype "bidirectional"))
    )
    (net (code "52") (name "N21_P") (class "Default")
      (node (ref "SENSOR") (pin "H17") (pinfunction "OUT52_N_H17") (pintype "output"))
      (node (ref "X-NORTH") (pin "75") (pinfunction "75_75") (pintype "bidirectional"))
    )
    (net (code "53") (name "N22_N") (class "Default")
      (node (ref "SENSOR") (pin "E18") (pinfunction "OUT51_P_E18") (pintype "output"))
      (node (ref "X-NORTH") (pin "82") (pinfunction "82_82") (pintype "bidirectional"))
    )
    (net (code "54") (name "N22_P") (class "Default")
      (node (ref "SENSOR") (pin "E17") (pinfunction "OUT51_N_E17") (pintype "output"))
      (node (ref "X-NORTH") (pin "80") (pinfunction "80_80") (pintype "bidirectional"))
    )
    (net (code "55") (name "N23_N") (class "Default")
      (node (ref "SENSOR") (pin "G19") (pinfunction "OUT54_P_G19") (pintype "output"))
      (node (ref "X-NORTH") (pin "83") (pinfunction "83_83") (pintype "bidirectional"))
    )
    (net (code "56") (name "N23_P") (class "Default")
      (node (ref "SENSOR") (pin "G18") (pinfunction "OUT54_N_G18") (pintype "output"))
      (node (ref "X-NORTH") (pin "81") (pinfunction "81_81") (pintype "bidirectional"))
    )
    (net (code "57") (name "N24_N") (class "Default")
      (node (ref "SENSOR") (pin "F19") (pinfunction "OUT53_P_F19") (pintype "output"))
      (node (ref "X-NORTH") (pin "88") (pinfunction "88_88") (pintype "bidirectional"))
    )
    (net (code "58") (name "N24_P") (class "Default")
      (node (ref "SENSOR") (pin "F18") (pinfunction "OUT53_N_F18") (pintype "output"))
      (node (ref "X-NORTH") (pin "86") (pinfunction "86_86") (pintype "bidirectional"))
    )
    (net (code "59") (name "N25_N") (class "Default")
      (node (ref "SENSOR") (pin "H20") (pinfunction "OUT56_P_H20") (pintype "output"))
      (node (ref "X-NORTH") (pin "89") (pinfunction "89_89") (pintype "bidirectional"))
    )
    (net (code "60") (name "N25_P") (class "Default")
      (node (ref "SENSOR") (pin "H19") (pinfunction "OUT56_N_H19") (pintype "output"))
      (node (ref "X-NORTH") (pin "87") (pinfunction "87_87") (pintype "bidirectional"))
    )
    (net (code "61") (name "N26_N") (class "Default")
      (node (ref "SENSOR") (pin "E20") (pinfunction "OUT55_P_E20") (pintype "output"))
      (node (ref "X-NORTH") (pin "94") (pinfunction "94_94") (pintype "bidirectional"))
    )
    (net (code "62") (name "N26_P") (class "Default")
      (node (ref "SENSOR") (pin "E19") (pinfunction "OUT55_N_E19") (pintype "output"))
      (node (ref "X-NORTH") (pin "92") (pinfunction "92_92") (pintype "bidirectional"))
    )
    (net (code "63") (name "N27_N") (class "Default")
      (node (ref "SENSOR") (pin "G21") (pinfunction "OUT58_P_G21") (pintype "output"))
      (node (ref "X-NORTH") (pin "95") (pinfunction "95_95") (pintype "bidirectional"))
    )
    (net (code "64") (name "N27_P") (class "Default")
      (node (ref "SENSOR") (pin "G20") (pinfunction "OUT58_N_G20") (pintype "output"))
      (node (ref "X-NORTH") (pin "93") (pinfunction "93_93") (pintype "bidirectional"))
    )
    (net (code "65") (name "N28_N") (class "Default")
      (node (ref "SENSOR") (pin "F21") (pinfunction "OUT57_P_F21") (pintype "output"))
      (node (ref "X-NORTH") (pin "100") (pinfunction "100_100") (pintype "bidirectional"))
    )
    (net (code "66") (name "N28_P") (class "Default")
      (node (ref "SENSOR") (pin "F20") (pinfunction "OUT57_N_F20") (pintype "output"))
      (node (ref "X-NORTH") (pin "98") (pinfunction "98_98") (pintype "bidirectional"))
    )
    (net (code "67") (name "N29_N") (class "Default")
      (node (ref "SENSOR") (pin "G23") (pinfunction "OUT61_P_G23") (pintype "output"))
      (node (ref "X-NORTH") (pin "101") (pinfunction "101_101") (pintype "bidirectional"))
    )
    (net (code "68") (name "N29_P") (class "Default")
      (node (ref "SENSOR") (pin "G22") (pinfunction "OUT61_N_G22") (pintype "output"))
      (node (ref "X-NORTH") (pin "99") (pinfunction "99_99") (pintype "bidirectional"))
    )
    (net (code "69") (name "N30_N") (class "Default")
      (node (ref "SENSOR") (pin "E22") (pinfunction "OUT59_P_E22") (pintype "output"))
      (node (ref "X-NORTH") (pin "106") (pinfunction "106_106") (pintype "bidirectional"))
    )
    (net (code "70") (name "N30_P") (class "Default")
      (node (ref "SENSOR") (pin "E21") (pinfunction "OUT59_N_E21") (pintype "output"))
      (node (ref "X-NORTH") (pin "104") (pinfunction "104_104") (pintype "bidirectional"))
    )
    (net (code "71") (name "N31_N") (class "Default")
      (node (ref "SENSOR") (pin "H24") (pinfunction "OUT63_P_H24") (pintype "output"))
      (node (ref "X-NORTH") (pin "107") (pinfunction "107_107") (pintype "bidirectional"))
    )
    (net (code "72") (name "N31_P") (class "Default")
      (node (ref "SENSOR") (pin "H23") (pinfunction "OUT63_N_H23") (pintype "output"))
      (node (ref "X-NORTH") (pin "105") (pinfunction "105_105") (pintype "bidirectional"))
    )
    (net (code "73") (name "N32_N") (class "Default")
      (node (ref "SENSOR") (pin "F23") (pinfunction "OUT60_P_F23") (pintype "output"))
      (node (ref "X-NORTH") (pin "112") (pinfunction "112_112") (pintype "bidirectional"))
    )
    (net (code "74") (name "N32_P") (class "Default")
      (node (ref "SENSOR") (pin "F22") (pinfunction "OUT60_N_F22") (pintype "output"))
      (node (ref "X-NORTH") (pin "110") (pinfunction "110_110") (pintype "bidirectional"))
    )
    (net (code "75") (name "N33_N") (class "Default")
      (node (ref "SENSOR") (pin "G25") (pinfunction "OUT64_P_G25") (pintype "output"))
      (node (ref "X-NORTH") (pin "113") (pinfunction "113_113") (pintype "bidirectional"))
    )
    (net (code "76") (name "N33_P") (class "Default")
      (node (ref "SENSOR") (pin "G24") (pinfunction "OUT64_N_G24") (pintype "output"))
      (node (ref "X-NORTH") (pin "111") (pinfunction "111_111") (pintype "bidirectional"))
    )
    (net (code "77") (name "N34_N") (class "Default")
      (node (ref "SENSOR") (pin "E24") (pinfunction "OUT62_P_E24") (pintype "output"))
      (node (ref "X-NORTH") (pin "118") (pinfunction "118_118") (pintype "bidirectional"))
    )
    (net (code "78") (name "N34_P") (class "Default")
      (node (ref "SENSOR") (pin "E23") (pinfunction "OUT62_N_E23") (pintype "output"))
      (node (ref "X-NORTH") (pin "116") (pinfunction "116_116") (pintype "bidirectional"))
    )
    (net (code "79") (name "N35_N") (class "Default")
      (node (ref "U6") (pin "4") (pinfunction "A4_4") (pintype "bidirectional"))
      (node (ref "X-NORTH") (pin "119") (pinfunction "119_119") (pintype "bidirectional"))
    )
    (net (code "80") (name "N35_P") (class "Default")
      (node (ref "U6") (pin "3") (pinfunction "A3_3") (pintype "bidirectional"))
      (node (ref "X-NORTH") (pin "117") (pinfunction "117_117") (pintype "bidirectional"))
    )
    (net (code "81") (name "N36_N") (class "Default")
      (node (ref "X-NORTH") (pin "124") (pinfunction "124_124") (pintype "bidirectional"))
    )
    (net (code "82") (name "N36_P") (class "Default")
      (node (ref "X-NORTH") (pin "122") (pinfunction "122_122") (pintype "bidirectional"))
    )
    (net (code "83") (name "N37_N") (class "Default")
      (node (ref "U5") (pin "3") (pinfunction "A3_3") (pintype "bidirectional"))
      (node (ref "X-NORTH") (pin "125") (pinfunction "125_125") (pintype "bidirectional"))
    )
    (net (code "84") (name "N37_P") (class "Default")
      (node (ref "U5") (pin "4") (pinfunction "A4_4") (pintype "bidirectional"))
      (node (ref "X-NORTH") (pin "123") (pinfunction "123_123") (pintype "bidirectional"))
    )
    (net (code "85") (name "N38_N") (class "Default")
      (node (ref "U6") (pin "2") (pinfunction "A2_2") (pintype "bidirectional"))
      (node (ref "X-NORTH") (pin "130") (pinfunction "130_130") (pintype "bidirectional"))
    )
    (net (code "86") (name "N38_P") (class "Default")
      (node (ref "U6") (pin "1") (pinfunction "A1_1") (pintype "bidirectional"))
      (node (ref "X-NORTH") (pin "128") (pinfunction "128_128") (pintype "bidirectional"))
    )
    (net (code "87") (name "N39_N") (class "Default")
      (node (ref "U5") (pin "1") (pinfunction "A1_1") (pintype "bidirectional"))
      (node (ref "X-NORTH") (pin "131") (pinfunction "131_131") (pintype "bidirectional"))
    )
    (net (code "88") (name "N39_P") (class "Default")
      (node (ref "U5") (pin "2") (pinfunction "A2_2") (pintype "bidirectional"))
      (node (ref "X-NORTH") (pin "129") (pinfunction "129_129") (pintype "bidirectional"))
    )
    (net (code "89") (name "N_CHK_V") (class "Default")
      (node (ref "C2") (pin "1") (pinfunction "1_1") (pintype "passive"))
      (node (ref "C3") (pin "1") (pinfunction "1_1") (pintype "passive"))
      (node (ref "C4") (pin "1") (pinfunction "1_1") (pintype "passive"))
      (node (ref "R19") (pin "1") (pinfunction "1_1") (pintype "passive"))
      (node (ref "TP1") (pin "TP") (pinfunction "TP_TP") (pintype "input"))
      (node (ref "UNE") (pin "8") (pinfunction "VDD_8") (pintype "power_in"))
      (node (ref "UNN") (pin "8") (pinfunction "VDD_8") (pintype "power_in"))
      (node (ref "UNW") (pin "8") (pinfunction "VDD_8") (pintype "power_in"))
      (node (ref "X-NORTH") (pin "10") (pinfunction "10_10") (pintype "bidirectional"))
      (node (ref "X-NORTH") (pin "8") (pinfunction "8_8") (pintype "bidirectional"))
    )
    (net (code "90") (name "N_I2C_V") (class "Default")
      (node (ref "C1") (pin "1") (pinfunction "1_1") (pintype "passive"))
      (node (ref "R1X") (pin "1") (pinfunction "1_1") (pintype "passive"))
      (node (ref "UEP") (pin "8") (pinfunction "VCC_8") (pintype "power_in"))
      (node (ref "X-NORTH") (pin "135") (pinfunction "135_135") (pintype "bidirectional"))
      (node (ref "X-NORTH") (pin "137") (pinfunction "137_137") (pintype "bidirectional"))
    )
    (net (code "91") (name "N_REF") (class "Default")
      (node (ref "R19") (pin "2") (pinfunction "2_2") (pintype "passive"))
      (node (ref "TP2") (pin "TP") (pinfunction "TP_TP") (pintype "input"))
      (node (ref "U1") (pin "1") (pinfunction "CATHODE_1") (pintype "output"))
      (node (ref "U1") (pin "3") (pinfunction "REF_3") (pintype "input"))
      (node (ref "UNE") (pin "2") (pinfunction "VINA-_2") (pintype "input"))
      (node (ref "UNE") (pin "5") (pinfunction "VINB+_5") (pintype "input"))
      (node (ref "UNN") (pin "2") (pinfunction "VINA-_2") (pintype "input"))
      (node (ref "UNN") (pin "5") (pinfunction "VINB+_5") (pintype "input"))
      (node (ref "UNW") (pin "2") (pinfunction "VINA-_2") (pintype "input"))
      (node (ref "UNW") (pin "5") (pinfunction "VINB+_5") (pintype "input"))
    )
    (net (code "92") (name "N_SCK") (class "Default")
      (node (ref "U4") (pin "15") (pinfunction "1B1_15") (pintype "output"))
      (node (ref "X-NORTH") (pin "144") (pinfunction "144_144") (pintype "bidirectional"))
    )
    (net (code "93") (name "N_SCL") (class "Default")
      (node (ref "UEP") (pin "6") (pinfunction "SCL_6") (pintype "input"))
      (node (ref "X-NORTH") (pin "143") (pinfunction "143_143") (pintype "bidirectional"))
    )
    (net (code "94") (name "N_SDA") (class "Default")
      (node (ref "UEP") (pin "5") (pinfunction "SDA_5") (pintype "bidirectional"))
      (node (ref "X-NORTH") (pin "141") (pinfunction "141_141") (pintype "bidirectional"))
    )
    (net (code "95") (name "N_SDI") (class "Default")
      (node (ref "U4") (pin "13") (pinfunction "2B1_13") (pintype "output"))
      (node (ref "X-NORTH") (pin "140") (pinfunction "140_140") (pintype "bidirectional"))
    )
    (net (code "96") (name "N_SDO") (class "Default")
      (node (ref "U4") (pin "14") (pinfunction "1B2_14") (pintype "output"))
      (node (ref "X-NORTH") (pin "142") (pinfunction "142_142") (pintype "bidirectional"))
    )
    (net (code "97") (name "N_SPI_V") (class "Default")
      (node (ref "C59") (pin "1") (pinfunction "1_1") (pintype "passive"))
      (node (ref "U4") (pin "2") (pinfunction "VCCB_2") (pintype "power_in"))
      (node (ref "X-NORTH") (pin "134") (pinfunction "134_134") (pintype "bidirectional"))
      (node (ref "X-NORTH") (pin "136") (pinfunction "136_136") (pintype "bidirectional"))
    )
    (net (code "98") (name "N_VE") (class "Default")
      (node (ref "C50") (pin "1") (pinfunction "1_1") (pintype "passive"))
      (node (ref "C51") (pin "1") (pinfunction "1_1") (pintype "passive"))
      (node (ref "C52") (pin "1") (pinfunction "1_1") (pintype "passive"))
      (node (ref "C53") (pin "1") (pinfunction "1_1") (pintype "passive"))
      (node (ref "C54") (pin "1") (pinfunction "1_1") (pintype "passive"))
      (node (ref "C55") (pin "1") (pinfunction "1_1") (pintype "passive"))
      (node (ref "C56") (pin "1") (pinfunction "1_1") (pintype "passive"))
      (node (ref "C67") (pin "1") (pinfunction "1_1") (pintype "passive"))
      (node (ref "C69") (pin "1") (pinfunction "1_1") (pintype "passive"))
      (node (ref "C75") (pin "1") (pinfunction "1_1") (pintype "passive"))
      (node (ref "C76") (pin "1") (pinfunction "1_1") (pintype "passive"))
      (node (ref "C77") (pin "1") (pinfunction "1_1") (pintype "passive"))
      (node (ref "C84") (pin "1") (pinfunction "1_1") (pintype "passive"))
      (node (ref "C85") (pin "1") (pinfunction "1_1") (pintype "passive"))
      (node (ref "C86") (pin "1") (pinfunction "1_1") (pintype "passive"))
      (node (ref "SENSOR") (pin "C26") (pinfunction "VDD33_C26") (pintype "power_in"))
      (node (ref "SENSOR") (pin "C27") (pinfunction "VDD33_C27") (pintype "power_in"))
      (node (ref "SENSOR") (pin "D26") (pinfunction "VDD33_D26") (pintype "power_in"))
      (node (ref "SENSOR") (pin "D3") (pinfunction "VDD33_D3") (pintype "power_in"))
      (node (ref "SENSOR") (pin "E26") (pinfunction "VDD33_E26") (pintype "power_in"))
      (node (ref "SENSOR") (pin "F26") (pinfunction "VDD33_F26") (pintype "power_in"))
      (node (ref "SENSOR") (pin "F5") (pinfunction "VDD33_F5") (pintype "power_in"))
      (node (ref "TP7") (pin "TP") (pinfunction "TP_TP") (pintype "input"))
      (node (ref "U4") (pin "3") (pinfunction "VCCA_3") (pintype "power_in"))
      (node (ref "U4") (pin "5") (pinfunction "2DIR_5") (pintype "input"))
      (node (ref "U5") (pin "13") (pinfunction "VCCB_13") (pintype "power_in"))
      (node (ref "U6") (pin "13") (pinfunction "VCCB_13") (pintype "power_in"))
      (node (ref "X-NORTH") (pin "109") (pinfunction "109_109") (pintype "bidirectional"))
      (node (ref "X-NORTH") (pin "115") (pinfunction "115_115") (pintype "bidirectional"))
      (node (ref "X-NORTH") (pin "121") (pinfunction "121_121") (pintype "bidirectional"))
      (node (ref "X-NORTH") (pin "127") (pinfunction "127_127") (pintype "bidirectional"))
      (node (ref "X-NORTH") (pin "133") (pinfunction "133_133") (pintype "bidirectional"))
    )
    (net (code "99") (name "N_VE_CV") (class "Default")
      (node (ref "C10") (pin "1") (pinfunction "1_1") (pintype "passive"))
      (node (ref "R7") (pin "1") (pinfunction "1_1") (pintype "passive"))
      (node (ref "X-NORTH") (pin "6") (pinfunction "6_6") (pintype "bidirectional"))
    )
    (net (code "100") (name "N_VE_OV") (class "Default")
      (node (ref "UNE") (pin "7") (pinfunction "OUTB_7") (pintype "output"))
      (node (ref "X-NORTH") (pin "5") (pinfunction "5_5") (pintype "bidirectional"))
    )
    (net (code "101") (name "N_VE_UV") (class "Default")
      (node (ref "UNE") (pin "1") (pinfunction "OUTA_1") (pintype "output"))
      (node (ref "X-NORTH") (pin "11") (pinfunction "11_11") (pintype "bidirectional"))
    )
    (net (code "102") (name "N_VN") (class "Default")
      (node (ref "C31") (pin "1") (pinfunction "1_1") (pintype "passive"))
      (node (ref "C32") (pin "1") (pinfunction "1_1") (pintype "passive"))
      (node (ref "C33") (pin "1") (pinfunction "1_1") (pintype "passive"))
      (node (ref "C34") (pin "1") (pinfunction "1_1") (pintype "passive"))
      (node (ref "C35") (pin "1") (pinfunction "1_1") (pintype "passive"))
      (node (ref "C36") (pin "1") (pinfunction "1_1") (pintype "passive"))
      (node (ref "C37") (pin "1") (pinfunction "1_1") (pintype "passive"))
      (node (ref "C38") (pin "1") (pinfunction "1_1") (pintype "passive"))
      (node (ref "C39") (pin "1") (pinfunction "1_1") (pintype "passive"))
      (node (ref "C40") (pin "1") (pinfunction "1_1") (pintype "passive"))
      (node (ref "C41") (pin "1") (pinfunction "1_1") (pintype "passive"))
      (node (ref "C42") (pin "1") (pinfunction "1_1") (pintype "passive"))
      (node (ref "C43") (pin "1") (pinfunction "1_1") (pintype "passive"))
      (node (ref "C44") (pin "1") (pinfunction "1_1") (pintype "passive"))
      (node (ref "C68") (pin "1") (pinfunction "1_1") (pintype "passive"))
      (node (ref "C70") (pin "1") (pinfunction "1_1") (pintype "passive"))
      (node (ref "C78") (pin "1") (pinfunction "1_1") (pintype "passive"))
      (node (ref "C79") (pin "1") (pinfunction "1_1") (pintype "passive"))
      (node (ref "C80") (pin "1") (pinfunction "1_1") (pintype "passive"))
      (node (ref "C87") (pin "1") (pinfunction "1_1") (pintype "passive"))
      (node (ref "C88") (pin "1") (pinfunction "1_1") (pintype "passive"))
      (node (ref "C89") (pin "1") (pinfunction "1_1") (pintype "passive"))
      (node (ref "SENSOR") (pin "A10") (pinfunction "VDD18_A10") (pintype "power_in"))
      (node (ref "SENSOR") (pin "A15") (pinfunction "VDD18_A15") (pintype "power_in"))
      (node (ref "SENSOR") (pin "A16") (pinfunction "VDD18_A16") (pintype "power_in"))
      (node (ref "SENSOR") (pin "A22") (pinfunction "VDD18_A22") (pintype "power_in"))
      (node (ref "SENSOR") (pin "A26") (pinfunction "VDD18_A26") (pintype "power_in"))
      (node (ref "SENSOR") (pin "A27") (pinfunction "VDD18_A27") (pintype "power_in"))
      (node (ref "SENSOR") (pin "B4") (pinfunction "VDD18_B4") (pintype "power_in"))
      (node (ref "SENSOR") (pin "E1") (pinfunction "VDD18_PLL_E1") (pintype "power_in"))
      (node (ref "SENSOR") (pin "H10") (pinfunction "VDD18_H10") (pintype "power_in"))
      (node (ref "SENSOR") (pin "H15") (pinfunction "VDD18_H15") (pintype "power_in"))
      (node (ref "SENSOR") (pin "H16") (pinfunction "VDD18_H16") (pintype "power_in"))
      (node (ref "SENSOR") (pin "H22") (pinfunction "VDD18_H22") (pintype "power_in"))
      (node (ref "SENSOR") (pin "H26") (pinfunction "VDD18_H26") (pintype "power_in"))
      (node (ref "SENSOR") (pin "H5") (pinfunction "VDD18_H5") (pintype "power_in"))
      (node (ref "TP5") (pin "TP") (pinfunction "TP_TP") (pintype "input"))
      (node (ref "U5") (pin "14") (pinfunction "VCCA_14") (pintype "power_in"))
      (node (ref "U5") (pin "15") (pinfunction "DIR1_15") (pintype "input"))
      (node (ref "U5") (pin "16") (pinfunction "DIR2_16") (pintype "input"))
      (node (ref "U5") (pin "5") (pinfunction "DIR3_5") (pintype "input"))
      (node (ref "U6") (pin "14") (pinfunction "VCCA_14") (pintype "power_in"))
      (node (ref "U6") (pin "16") (pinfunction "DIR2_16") (pintype "input"))
      (node (ref "X-NORTH") (pin "49") (pinfunction "49_49") (pintype "bidirectional"))
      (node (ref "X-NORTH") (pin "55") (pinfunction "55_55") (pintype "bidirectional"))
      (node (ref "X-NORTH") (pin "61") (pinfunction "61_61") (pintype "bidirectional"))
      (node (ref "X-NORTH") (pin "67") (pinfunction "67_67") (pintype "bidirectional"))
      (node (ref "X-NORTH") (pin "73") (pinfunction "73_73") (pintype "bidirectional"))
      (node (ref "X-NORTH") (pin "79") (pinfunction "79_79") (pintype "bidirectional"))
      (node (ref "X-NORTH") (pin "85") (pinfunction "85_85") (pintype "bidirectional"))
      (node (ref "X-NORTH") (pin "91") (pinfunction "91_91") (pintype "bidirectional"))
      (node (ref "X-NORTH") (pin "97") (pinfunction "97_97") (pintype "bidirectional"))
    )
    (net (code "103") (name "N_VN_CV") (class "Default")
      (node (ref "C9") (pin "1") (pinfunction "1_1") (pintype "passive"))
      (node (ref "R4") (pin "1") (pinfunction "1_1") (pintype "passive"))
      (node (ref "X-NORTH") (pin "4") (pinfunction "4_4") (pintype "bidirectional"))
    )
    (net (code "104") (name "N_VN_OV") (class "Default")
      (node (ref "UNN") (pin "7") (pinfunction "OUTB_7") (pintype "output"))
      (node (ref "X-NORTH") (pin "3") (pinfunction "3_3") (pintype "bidirectional"))
    )
    (net (code "105") (name "N_VN_UV") (class "Default")
      (node (ref "UNN") (pin "1") (pinfunction "OUTA_1") (pintype "output"))
      (node (ref "X-NORTH") (pin "9") (pinfunction "9_9") (pintype "bidirectional"))
    )
    (net (code "106") (name "N_VW") (class "Default")
      (node (ref "C57") (pin "1") (pinfunction "1_1") (pintype "passive"))
      (node (ref "C58") (pin "1") (pinfunction "1_1") (pintype "passive"))
      (node (ref "C92") (pin "1") (pinfunction "1_1") (pintype "passive"))
      (node (ref "SENSOR") (pin "E2") (pinfunction "VDD_RES_E2") (pintype "power_in"))
      (node (ref "SENSOR") (pin "G4") (pinfunction "VDD_RES_G4") (pintype "power_in"))
      (node (ref "TP8") (pin "TP") (pinfunction "TP_TP") (pintype "input"))
      (node (ref "X-NORTH") (pin "13") (pinfunction "13_13") (pintype "bidirectional"))
      (node (ref "X-NORTH") (pin "19") (pinfunction "19_19") (pintype "bidirectional"))
      (node (ref "X-NORTH") (pin "25") (pinfunction "25_25") (pintype "bidirectional"))
      (node (ref "X-NORTH") (pin "31") (pinfunction "31_31") (pintype "bidirectional"))
      (node (ref "X-NORTH") (pin "37") (pinfunction "37_37") (pintype "bidirectional"))
    )
    (net (code "107") (name "N_VW_CV") (class "Default")
      (node (ref "C8") (pin "1") (pinfunction "1_1") (pintype "passive"))
      (node (ref "R1") (pin "1") (pinfunction "1_1") (pintype "passive"))
      (node (ref "X-NORTH") (pin "2") (pinfunction "2_2") (pintype "bidirectional"))
    )
    (net (code "108") (name "N_VW_OV") (class "Default")
      (node (ref "UNW") (pin "7") (pinfunction "OUTB_7") (pintype "output"))
      (node (ref "X-NORTH") (pin "1") (pinfunction "1_1") (pintype "bidirectional"))
    )
    (net (code "109") (name "N_VW_UV") (class "Default")
      (node (ref "UNW") (pin "1") (pinfunction "OUTA_1") (pintype "output"))
      (node (ref "X-NORTH") (pin "7") (pinfunction "7_7") (pintype "bidirectional"))
    )
    (net (code "110") (name "Net-(SENSORB-CMDN)") (class "Default")
      (node (ref "C61") (pin "1") (pinfunction "1_1") (pintype "passive"))
      (node (ref "SENSOR") (pin "F1") (pinfunction "CMDN_F1") (pintype "bidirectional"))
    )
    (net (code "111") (name "Net-(SENSORB-CMDP)") (class "Default")
      (node (ref "C22") (pin "2") (pinfunction "2_2") (pintype "passive"))
      (node (ref "SENSOR") (pin "F2") (pinfunction "CMDP_F2") (pintype "bidirectional"))
    )
    (net (code "112") (name "Net-(SENSORB-CMDP_COMP)") (class "Default")
      (node (ref "C28") (pin "2") (pinfunction "2_2") (pintype "passive"))
      (node (ref "SENSOR") (pin "H3") (pinfunction "CMDP_COMP_H3") (pintype "bidirectional"))
    )
    (net (code "113") (name "Net-(SENSORB-CMDP_COMP_INV)") (class "Default")
      (node (ref "C27") (pin "2") (pinfunction "2_2") (pintype "passive"))
      (node (ref "SENSOR") (pin "F3") (pinfunction "CMDP_COMP_INV_F3") (pintype "bidirectional"))
    )
    (net (code "114") (name "Net-(SENSORB-CMD_COLAMP)") (class "Default")
      (node (ref "C25") (pin "2") (pinfunction "2_2") (pintype "passive"))
      (node (ref "SENSOR") (pin "C6") (pinfunction "CMD_COLAMP_C6") (pintype "bidirectional"))
    )
    (net (code "115") (name "Net-(SENSORB-CMD_COL_LOAD)") (class "Default")
      (node (ref "C23") (pin "2") (pinfunction "2_2") (pintype "passive"))
      (node (ref "SENSOR") (pin "B1") (pinfunction "CMD_COL_LOAD_B1") (pintype "bidirectional"))
    )
    (net (code "116") (name "Net-(SENSORB-CMD_COL_PC)") (class "Default")
      (node (ref "C26") (pin "2") (pinfunction "2_2") (pintype "passive"))
      (node (ref "SENSOR") (pin "D1") (pinfunction "CMD_COL_PC_D1") (pintype "bidirectional"))
    )
    (net (code "117") (name "Net-(SENSORB-CMD_LVDS)") (class "Default")
      (node (ref "C62") (pin "1") (pinfunction "1_1") (pintype "passive"))
      (node (ref "SENSOR") (pin "C1") (pinfunction "CMD_LVDS_C1") (pintype "bidirectional"))
    )
    (net (code "118") (name "Net-(SENSORB-CMD_RAMP)") (class "Default")
      (node (ref "C24") (pin "2") (pinfunction "2_2") (pintype "passive"))
      (node (ref "SENSOR") (pin "B29") (pinfunction "CMD_RAMP_B29") (pintype "bidirectional"))
    )
    (net (code "119") (name "Net-(SENSORB-VBGAP)") (class "Default")
      (node (ref "C64") (pin "1") (pinfunction "1_1") (pintype "passive"))
      (node (ref "SENSOR") (pin "C29") (pinfunction "VBGAP_C29") (pintype "bidirectional"))
    )
    (net (code "120") (name "Net-(SENSORB-VCLAMP)") (class "Default")
      (node (ref "C63") (pin "1") (pinfunction "1_1") (pintype "passive"))
      (node (ref "SENSOR") (pin "D4") (pinfunction "VCLAMP_D4") (pintype "bidirectional"))
    )
    (net (code "121") (name "Net-(SENSORB-VCLAMP_ADC)") (class "Default")
      (node (ref "C60") (pin "1") (pinfunction "1_1") (pintype "passive"))
      (node (ref "SENSOR") (pin "G2") (pinfunction "VCLAMP_ADC_G2") (pintype "bidirectional"))
    )
    (net (code "122") (name "Net-(SENSORB-VPCH_H)") (class "Default")
      (node (ref "C71") (pin "1") (pinfunction "1_1") (pintype "passive"))
      (node (ref "SENSOR") (pin "C4") (pinfunction "VPCH_H_C4") (pintype "bidirectional"))
    )
    (net (code "123") (name "Net-(SENSORB-VPCH_L)") (class "Default")
      (node (ref "C14") (pin "1") (pinfunction "1_1") (pintype "passive"))
      (node (ref "SENSOR") (pin "A4") (pinfunction "VPCH_L_A4") (pintype "bidirectional"))
    )
    (net (code "124") (name "Net-(SENSORB-VREF)") (class "Default")
      (node (ref "C29") (pin "1") (pinfunction "1_1") (pintype "passive"))
      (node (ref "SENSOR") (pin "A3") (pinfunction "VREF_A3") (pintype "bidirectional"))
    )
    (net (code "125") (name "Net-(SENSORB-VREF_ADC)") (class "Default")
      (node (ref "C30") (pin "1") (pinfunction "1_1") (pintype "passive"))
      (node (ref "SENSOR") (pin "B3") (pinfunction "VREF_ADC_B3") (pintype "bidirectional"))
    )
    (net (code "126") (name "Net-(SENSORB-VRES_L)") (class "Default")
      (node (ref "C15") (pin "1") (pinfunction "1_1") (pintype "passive"))
      (node (ref "SENSOR") (pin "D5") (pinfunction "VRES_L_D5") (pintype "bidirectional"))
    )
    (net (code "127") (name "Net-(SENSORB-VTF_LOW0)") (class "Default")
      (node (ref "C18") (pin "1") (pinfunction "1_1") (pintype "passive"))
      (node (ref "SENSOR") (pin "C5") (pinfunction "VTF_LOW0_C5") (pintype "bidirectional"))
    )
    (net (code "128") (name "Net-(SENSORB-VTF_LOW1)") (class "Default")
      (node (ref "C19") (pin "1") (pinfunction "1_1") (pintype "passive"))
      (node (ref "SENSOR") (pin "D6") (pinfunction "VTF_LOW1_D6") (pintype "bidirectional"))
    )
    (net (code "129") (name "Net-(SENSORB-VTF_LOW2)") (class "Default")
      (node (ref "C20") (pin "1") (pinfunction "1_1") (pintype "passive"))
      (node (ref "SENSOR") (pin "B30") (pinfunction "VTF_LOW2_B30") (pintype "bidirectional"))
    )
    (net (code "130") (name "Net-(SENSORB-VTF_LOW3)") (class "Default")
      (node (ref "C21") (pin "1") (pinfunction "1_1") (pintype "passive"))
      (node (ref "SENSOR") (pin "C30") (pinfunction "VTF_LOW3_C30") (pintype "bidirectional"))
    )
    (net (code "131") (name "Net-(U3-ADJ)") (class "Default")
      (node (ref "R21") (pin "1") (pinfunction "1_1") (pintype "passive"))
      (node (ref "R22") (pin "2") (pinfunction "2_2") (pintype "passive"))
      (node (ref "U3") (pin "5") (pinfunction "ADJ_5") (pintype "input"))
    )
    (net (code "132") (name "Net-(UEP-WP)") (class "Default")
      (node (ref "R1X") (pin "2") (pinfunction "2_2") (pintype "passive"))
      (node (ref "R2X") (pin "1") (pinfunction "1_1") (pintype "passive"))
      (node (ref "UEP") (pin "7") (pinfunction "WP_7") (pintype "input"))
    )
    (net (code "133") (name "Net-(UNE-VINA+)") (class "Default")
      (node (ref "R7") (pin "2") (pinfunction "2_2") (pintype "passive"))
      (node (ref "R8") (pin "1") (pinfunction "1_1") (pintype "passive"))
      (node (ref "UNE") (pin "3") (pinfunction "VINA+_3") (pintype "input"))
    )
    (net (code "134") (name "Net-(UNE-VINB-)") (class "Default")
      (node (ref "R8") (pin "2") (pinfunction "2_2") (pintype "passive"))
      (node (ref "R9") (pin "1") (pinfunction "1_1") (pintype "passive"))
      (node (ref "UNE") (pin "6") (pinfunction "VINB-_6") (pintype "input"))
    )
    (net (code "135") (name "Net-(UNN-VINA+)") (class "Default")
      (node (ref "R4") (pin "2") (pinfunction "2_2") (pintype "passive"))
      (node (ref "R5") (pin "1") (pinfunction "1_1") (pintype "passive"))
      (node (ref "UNN") (pin "3") (pinfunction "VINA+_3") (pintype "input"))
    )
    (net (code "136") (name "Net-(UNN-VINB-)") (class "Default")
      (node (ref "R5") (pin "2") (pinfunction "2_2") (pintype "passive"))
      (node (ref "R6") (pin "1") (pinfunction "1_1") (pintype "passive"))
      (node (ref "UNN") (pin "6") (pinfunction "VINB-_6") (pintype "input"))
    )
    (net (code "137") (name "Net-(UNW-VINA+)") (class "Default")
      (node (ref "R1") (pin "2") (pinfunction "2_2") (pintype "passive"))
      (node (ref "R2") (pin "1") (pinfunction "1_1") (pintype "passive"))
      (node (ref "UNW") (pin "3") (pinfunction "VINA+_3") (pintype "input"))
    )
    (net (code "138") (name "Net-(UNW-VINB-)") (class "Default")
      (node (ref "R2") (pin "2") (pinfunction "2_2") (pintype "passive"))
      (node (ref "R3") (pin "1") (pinfunction "1_1") (pintype "passive"))
      (node (ref "UNW") (pin "6") (pinfunction "VINB-_6") (pintype "input"))
    )
    (net (code "139") (name "Net-(USE-VINA+)") (class "Default")
      (node (ref "R10") (pin "2") (pinfunction "2_2") (pintype "passive"))
      (node (ref "R11") (pin "1") (pinfunction "1_1") (pintype "passive"))
      (node (ref "USE") (pin "3") (pinfunction "VINA+_3") (pintype "input"))
    )
    (net (code "140") (name "Net-(USE-VINB-)") (class "Default")
      (node (ref "R11") (pin "2") (pinfunction "2_2") (pintype "passive"))
      (node (ref "R12") (pin "1") (pinfunction "1_1") (pintype "passive"))
      (node (ref "USE") (pin "6") (pinfunction "VINB-_6") (pintype "input"))
    )
    (net (code "141") (name "Net-(USS-VINA+)") (class "Default")
      (node (ref "R13") (pin "2") (pinfunction "2_2") (pintype "passive"))
      (node (ref "R14") (pin "1") (pinfunction "1_1") (pintype "passive"))
      (node (ref "USS") (pin "3") (pinfunction "VINA+_3") (pintype "input"))
    )
    (net (code "142") (name "Net-(USS-VINB-)") (class "Default")
      (node (ref "R14") (pin "2") (pinfunction "2_2") (pintype "passive"))
      (node (ref "R15") (pin "1") (pinfunction "1_1") (pintype "passive"))
      (node (ref "USS") (pin "6") (pinfunction "VINB-_6") (pintype "input"))
    )
    (net (code "143") (name "Net-(USW-VINA+)") (class "Default")
      (node (ref "R16") (pin "2") (pinfunction "2_2") (pintype "passive"))
      (node (ref "R17") (pin "1") (pinfunction "1_1") (pintype "passive"))
      (node (ref "USW") (pin "3") (pinfunction "VINA+_3") (pintype "input"))
    )
    (net (code "144") (name "Net-(USW-VINB-)") (class "Default")
      (node (ref "R17") (pin "2") (pinfunction "2_2") (pintype "passive"))
      (node (ref "R18") (pin "1") (pinfunction "1_1") (pintype "passive"))
      (node (ref "USW") (pin "6") (pinfunction "VINB-_6") (pintype "input"))
    )
    (net (code "145") (name "S00_N") (class "Default")
      (node (ref "X-SOUTH") (pin "16") (pinfunction "16_16") (pintype "bidirectional"))
    )
    (net (code "146") (name "S00_P") (class "Default")
      (node (ref "X-SOUTH") (pin "14") (pinfunction "14_14") (pintype "bidirectional"))
    )
    (net (code "147") (name "S01_N") (class "Default")
      (node (ref "X-SOUTH") (pin "17") (pinfunction "17_17") (pintype "bidirectional"))
    )
    (net (code "148") (name "S01_P") (class "Default")
      (node (ref "X-SOUTH") (pin "15") (pinfunction "15_15") (pintype "bidirectional"))
    )
    (net (code "149") (name "S02_N") (class "Default")
      (node (ref "X-SOUTH") (pin "22") (pinfunction "22_22") (pintype "bidirectional"))
    )
    (net (code "150") (name "S02_P") (class "Default")
      (node (ref "X-SOUTH") (pin "20") (pinfunction "20_20") (pintype "bidirectional"))
    )
    (net (code "151") (name "S03_N") (class "Default")
      (node (ref "X-SOUTH") (pin "23") (pinfunction "23_23") (pintype "bidirectional"))
    )
    (net (code "152") (name "S03_P") (class "Default")
      (node (ref "X-SOUTH") (pin "21") (pinfunction "21_21") (pintype "bidirectional"))
    )
    (net (code "153") (name "S04_N") (class "Default")
      (node (ref "SENSOR") (pin "C24") (pinfunction "OUT32_N_C24") (pintype "output"))
      (node (ref "X-SOUTH") (pin "28") (pinfunction "28_28") (pintype "bidirectional"))
    )
    (net (code "154") (name "S04_P") (class "Default")
      (node (ref "SENSOR") (pin "C25") (pinfunction "OUT32_P_C25") (pintype "output"))
      (node (ref "X-SOUTH") (pin "26") (pinfunction "26_26") (pintype "bidirectional"))
    )
    (net (code "155") (name "S05_N") (class "Default")
      (node (ref "X-SOUTH") (pin "29") (pinfunction "29_29") (pintype "bidirectional"))
    )
    (net (code "156") (name "S05_P") (class "Default")
      (node (ref "X-SOUTH") (pin "27") (pinfunction "27_27") (pintype "bidirectional"))
    )
    (net (code "157") (name "S06_N") (class "Default")
      (node (ref "SENSOR") (pin "D23") (pinfunction "OUT30_N_D23") (pintype "output"))
      (node (ref "X-SOUTH") (pin "34") (pinfunction "34_34") (pintype "bidirectional"))
    )
    (net (code "158") (name "S06_P") (class "Default")
      (node (ref "SENSOR") (pin "D24") (pinfunction "OUT30_P_D24") (pintype "output"))
      (node (ref "X-SOUTH") (pin "32") (pinfunction "32_32") (pintype "bidirectional"))
    )
    (net (code "159") (name "S07_N") (class "Default")
      (node (ref "SENSOR") (pin "B24") (pinfunction "OUT31_N_B24") (pintype "output"))
      (node (ref "X-SOUTH") (pin "35") (pinfunction "35_35") (pintype "bidirectional"))
    )
    (net (code "160") (name "S07_P") (class "Default")
      (node (ref "SENSOR") (pin "B25") (pinfunction "OUT31_P_B25") (pintype "output"))
      (node (ref "X-SOUTH") (pin "33") (pinfunction "33_33") (pintype "bidirectional"))
    )
    (net (code "161") (name "S08_N") (class "Default")
      (node (ref "SENSOR") (pin "D21") (pinfunction "OUT27_N_D21") (pintype "output"))
      (node (ref "X-SOUTH") (pin "40") (pinfunction "40_40") (pintype "bidirectional"))
    )
    (net (code "162") (name "S08_P") (class "Default")
      (node (ref "SENSOR") (pin "D22") (pinfunction "OUT27_P_D22") (pintype "output"))
      (node (ref "X-SOUTH") (pin "38") (pinfunction "38_38") (pintype "bidirectional"))
    )
    (net (code "163") (name "S09_N") (class "Default")
      (node (ref "SENSOR") (pin "A23") (pinfunction "OUT29_N_A23") (pintype "output"))
      (node (ref "X-SOUTH") (pin "41") (pinfunction "41_41") (pintype "bidirectional"))
    )
    (net (code "164") (name "S09_P") (class "Default")
      (node (ref "SENSOR") (pin "A24") (pinfunction "OUT29_P_A24") (pintype "output"))
      (node (ref "X-SOUTH") (pin "39") (pinfunction "39_39") (pintype "bidirectional"))
    )
    (net (code "165") (name "S10_N") (class "Default")
      (node (ref "SENSOR") (pin "C21") (pinfunction "OUT28_N_C21") (pintype "output"))
      (node (ref "X-SOUTH") (pin "46") (pinfunction "46_46") (pintype "bidirectional"))
    )
    (net (code "166") (name "S10_P") (class "Default")
      (node (ref "SENSOR") (pin "C22") (pinfunction "OUT28_P_C22") (pintype "output"))
      (node (ref "X-SOUTH") (pin "44") (pinfunction "44_44") (pintype "bidirectional"))
    )
    (net (code "167") (name "S11_N") (class "Default")
      (node (ref "SENSOR") (pin "B20") (pinfunction "OUT26_N_B20") (pintype "output"))
      (node (ref "X-SOUTH") (pin "47") (pinfunction "47_47") (pintype "bidirectional"))
    )
    (net (code "168") (name "S11_P") (class "Default")
      (node (ref "SENSOR") (pin "B21") (pinfunction "OUT26_P_B21") (pintype "output"))
      (node (ref "X-SOUTH") (pin "45") (pinfunction "45_45") (pintype "bidirectional"))
    )
    (net (code "169") (name "S12_N") (class "Default")
      (node (ref "SENSOR") (pin "D19") (pinfunction "OUT24_N_D19") (pintype "output"))
      (node (ref "X-SOUTH") (pin "52") (pinfunction "52_52") (pintype "bidirectional"))
    )
    (net (code "170") (name "S12_P") (class "Default")
      (node (ref "SENSOR") (pin "D20") (pinfunction "OUT24_P_D20") (pintype "output"))
      (node (ref "X-SOUTH") (pin "50") (pinfunction "50_50") (pintype "bidirectional"))
    )
    (net (code "171") (name "S13_N") (class "Default")
      (node (ref "SENSOR") (pin "A19") (pinfunction "OUT23_N_A19") (pintype "output"))
      (node (ref "X-SOUTH") (pin "53") (pinfunction "53_53") (pintype "bidirectional"))
    )
    (net (code "172") (name "S13_P") (class "Default")
      (node (ref "SENSOR") (pin "A20") (pinfunction "OUT23_P_A20") (pintype "output"))
      (node (ref "X-SOUTH") (pin "51") (pinfunction "51_51") (pintype "bidirectional"))
    )
    (net (code "173") (name "S14_N") (class "Default")
      (node (ref "SENSOR") (pin "C19") (pinfunction "OUT25_N_C19") (pintype "output"))
      (node (ref "X-SOUTH") (pin "58") (pinfunction "58_58") (pintype "bidirectional"))
    )
    (net (code "174") (name "S14_P") (class "Default")
      (node (ref "SENSOR") (pin "C20") (pinfunction "OUT25_P_C20") (pintype "output"))
      (node (ref "X-SOUTH") (pin "56") (pinfunction "56_56") (pintype "bidirectional"))
    )
    (net (code "175") (name "S15_N") (class "Default")
      (node (ref "SENSOR") (pin "B18") (pinfunction "OUT22_N_B18") (pintype "output"))
      (node (ref "X-SOUTH") (pin "59") (pinfunction "59_59") (pintype "bidirectional"))
    )
    (net (code "176") (name "S15_P") (class "Default")
      (node (ref "SENSOR") (pin "B19") (pinfunction "OUT22_P_B19") (pintype "output"))
      (node (ref "X-SOUTH") (pin "57") (pinfunction "57_57") (pintype "bidirectional"))
    )
    (net (code "177") (name "S16_N") (class "Default")
      (node (ref "SENSOR") (pin "C17") (pinfunction "OUT21_N_C17") (pintype "output"))
      (node (ref "X-SOUTH") (pin "64") (pinfunction "64_64") (pintype "bidirectional"))
    )
    (net (code "178") (name "S16_P") (class "Default")
      (node (ref "SENSOR") (pin "C18") (pinfunction "OUT21_P_C18") (pintype "output"))
      (node (ref "X-SOUTH") (pin "62") (pinfunction "62_62") (pintype "bidirectional"))
    )
    (net (code "179") (name "S17_N") (class "Default")
      (node (ref "SENSOR") (pin "A17") (pinfunction "OUT19_N_A17") (pintype "output"))
      (node (ref "X-SOUTH") (pin "65") (pinfunction "65_65") (pintype "bidirectional"))
    )
    (net (code "180") (name "S17_P") (class "Default")
      (node (ref "SENSOR") (pin "A18") (pinfunction "OUT19_P_A18") (pintype "output"))
      (node (ref "X-SOUTH") (pin "63") (pinfunction "63_63") (pintype "bidirectional"))
    )
    (net (code "181") (name "S18_N") (class "Default")
      (node (ref "SENSOR") (pin "D17") (pinfunction "OUT20_N_D17") (pintype "output"))
      (node (ref "X-SOUTH") (pin "70") (pinfunction "70_70") (pintype "bidirectional"))
    )
    (net (code "182") (name "S18_P") (class "Default")
      (node (ref "SENSOR") (pin "D18") (pinfunction "OUT20_P_D18") (pintype "output"))
      (node (ref "X-SOUTH") (pin "68") (pinfunction "68_68") (pintype "bidirectional"))
    )
    (net (code "183") (name "S19_N") (class "Default")
      (node (ref "SENSOR") (pin "B16") (pinfunction "OUT18_N_B16") (pintype "output"))
      (node (ref "X-SOUTH") (pin "71") (pinfunction "71_71") (pintype "bidirectional"))
    )
    (net (code "184") (name "S19_P") (class "Default")
      (node (ref "SENSOR") (pin "B17") (pinfunction "OUT18_P_B17") (pintype "output"))
      (node (ref "X-SOUTH") (pin "69") (pinfunction "69_69") (pintype "bidirectional"))
    )
    (net (code "185") (name "S20_N") (class "Default")
      (node (ref "SENSOR") (pin "D15") (pinfunction "OUT17_N_D15") (pintype "output"))
      (node (ref "X-SOUTH") (pin "76") (pinfunction "76_76") (pintype "bidirectional"))
    )
    (net (code "186") (name "S20_P") (class "Default")
      (node (ref "SENSOR") (pin "D16") (pinfunction "OUT17_P_D16") (pintype "output"))
      (node (ref "X-SOUTH") (pin "74") (pinfunction "74_74") (pintype "bidirectional"))
    )
    (net (code "187") (name "S21_N") (class "Default")
      (node (ref "SENSOR") (pin "B14") (pinfunction "OUT16_N_B14") (pintype "output"))
      (node (ref "X-SOUTH") (pin "77") (pinfunction "77_77") (pintype "bidirectional"))
    )
    (net (code "188") (name "S21_P") (class "Default")
      (node (ref "SENSOR") (pin "B15") (pinfunction "OUT16_P_B15") (pintype "output"))
      (node (ref "X-SOUTH") (pin "75") (pinfunction "75_75") (pintype "bidirectional"))
    )
    (net (code "189") (name "S22_N") (class "Default")
      (node (ref "SENSOR") (pin "D13") (pinfunction "OUT15_N_D13") (pintype "output"))
      (node (ref "X-SOUTH") (pin "82") (pinfunction "82_82") (pintype "bidirectional"))
    )
    (net (code "190") (name "S22_P") (class "Default")
      (node (ref "SENSOR") (pin "D14") (pinfunction "OUT15_P_D14") (pintype "output"))
      (node (ref "X-SOUTH") (pin "80") (pinfunction "80_80") (pintype "bidirectional"))
    )
    (net (code "191") (name "S23_N") (class "Default")
      (node (ref "SENSOR") (pin "A13") (pinfunction "OUT13_N_A13") (pintype "output"))
      (node (ref "X-SOUTH") (pin "83") (pinfunction "83_83") (pintype "bidirectional"))
    )
    (net (code "192") (name "S23_P") (class "Default")
      (node (ref "SENSOR") (pin "A14") (pinfunction "OUT13_P_A14") (pintype "output"))
      (node (ref "X-SOUTH") (pin "81") (pinfunction "81_81") (pintype "bidirectional"))
    )
    (net (code "193") (name "S24_N") (class "Default")
      (node (ref "SENSOR") (pin "C13") (pinfunction "OUT14_N_C13") (pintype "output"))
      (node (ref "X-SOUTH") (pin "88") (pinfunction "88_88") (pintype "bidirectional"))
    )
    (net (code "194") (name "S24_P") (class "Default")
      (node (ref "SENSOR") (pin "C14") (pinfunction "OUT14_P_C14") (pintype "output"))
      (node (ref "X-SOUTH") (pin "86") (pinfunction "86_86") (pintype "bidirectional"))
    )
    (net (code "195") (name "S25_N") (class "Default")
      (node (ref "SENSOR") (pin "B12") (pinfunction "OUT12_N_B12") (pintype "output"))
      (node (ref "X-SOUTH") (pin "89") (pinfunction "89_89") (pintype "bidirectional"))
    )
    (net (code "196") (name "S25_P") (class "Default")
      (node (ref "SENSOR") (pin "B13") (pinfunction "OUT12_P_B13") (pintype "output"))
      (node (ref "X-SOUTH") (pin "87") (pinfunction "87_87") (pintype "bidirectional"))
    )
    (net (code "197") (name "S26_N") (class "Default")
      (node (ref "SENSOR") (pin "D11") (pinfunction "OUT10_N_D11") (pintype "output"))
      (node (ref "X-SOUTH") (pin "94") (pinfunction "94_94") (pintype "bidirectional"))
    )
    (net (code "198") (name "S26_P") (class "Default")
      (node (ref "SENSOR") (pin "D12") (pinfunction "OUT10_P_D12") (pintype "output"))
      (node (ref "X-SOUTH") (pin "92") (pinfunction "92_92") (pintype "bidirectional"))
    )
    (net (code "199") (name "S27_N") (class "Default")
      (node (ref "SENSOR") (pin "A11") (pinfunction "OUT9_N_A11") (pintype "output"))
      (node (ref "X-SOUTH") (pin "95") (pinfunction "95_95") (pintype "bidirectional"))
    )
    (net (code "200") (name "S27_P") (class "Default")
      (node (ref "SENSOR") (pin "A12") (pinfunction "OUT9_P_A12") (pintype "output"))
      (node (ref "X-SOUTH") (pin "93") (pinfunction "93_93") (pintype "bidirectional"))
    )
    (net (code "201") (name "S28_N") (class "Default")
      (node (ref "SENSOR") (pin "C11") (pinfunction "OUT11_N_C11") (pintype "output"))
      (node (ref "X-SOUTH") (pin "100") (pinfunction "100_100") (pintype "bidirectional"))
    )
    (net (code "202") (name "S28_P") (class "Default")
      (node (ref "SENSOR") (pin "C12") (pinfunction "OUT11_P_C12") (pintype "output"))
      (node (ref "X-SOUTH") (pin "98") (pinfunction "98_98") (pintype "bidirectional"))
    )
    (net (code "203") (name "S29_N") (class "Default")
      (node (ref "SENSOR") (pin "B10") (pinfunction "OUT8_N_B10") (pintype "output"))
      (node (ref "X-SOUTH") (pin "101") (pinfunction "101_101") (pintype "bidirectional"))
    )
    (net (code "204") (name "S29_P") (class "Default")
      (node (ref "SENSOR") (pin "B11") (pinfunction "OUT8_P_B11") (pintype "output"))
      (node (ref "X-SOUTH") (pin "99") (pinfunction "99_99") (pintype "bidirectional"))
    )
    (net (code "205") (name "S30_N") (class "Default")
      (node (ref "SENSOR") (pin "C9") (pinfunction "OUT7_N_C9") (pintype "output"))
      (node (ref "X-SOUTH") (pin "106") (pinfunction "106_106") (pintype "bidirectional"))
    )
    (net (code "206") (name "S30_P") (class "Default")
      (node (ref "SENSOR") (pin "C10") (pinfunction "OUT7_P_C10") (pintype "output"))
      (node (ref "X-SOUTH") (pin "104") (pinfunction "104_104") (pintype "bidirectional"))
    )
    (net (code "207") (name "S31_N") (class "Default")
      (node (ref "SENSOR") (pin "B8") (pinfunction "OUT5_N_B8") (pintype "output"))
      (node (ref "X-SOUTH") (pin "107") (pinfunction "107_107") (pintype "bidirectional"))
    )
    (net (code "208") (name "S31_P") (class "Default")
      (node (ref "SENSOR") (pin "B9") (pinfunction "OUT5_P_B9") (pintype "output"))
      (node (ref "X-SOUTH") (pin "105") (pinfunction "105_105") (pintype "bidirectional"))
    )
    (net (code "209") (name "S32_N") (class "Default")
      (node (ref "SENSOR") (pin "D9") (pinfunction "OUT6_N_D9") (pintype "output"))
      (node (ref "X-SOUTH") (pin "112") (pinfunction "112_112") (pintype "bidirectional"))
    )
    (net (code "210") (name "S32_P") (class "Default")
      (node (ref "SENSOR") (pin "D10") (pinfunction "OUT6_P_D10") (pintype "output"))
      (node (ref "X-SOUTH") (pin "110") (pinfunction "110_110") (pintype "bidirectional"))
    )
    (net (code "211") (name "S33_N") (class "Default")
      (node (ref "SENSOR") (pin "A7") (pinfunction "OUT2_N_A7") (pintype "output"))
      (node (ref "X-SOUTH") (pin "113") (pinfunction "113_113") (pintype "bidirectional"))
    )
    (net (code "212") (name "S33_P") (class "Default")
      (node (ref "SENSOR") (pin "A8") (pinfunction "OUT2_P_A8") (pintype "output"))
      (node (ref "X-SOUTH") (pin "111") (pinfunction "111_111") (pintype "bidirectional"))
    )
    (net (code "213") (name "S34_N") (class "Default")
      (node (ref "SENSOR") (pin "C7") (pinfunction "OUT4_N_C7") (pintype "output"))
      (node (ref "X-SOUTH") (pin "118") (pinfunction "118_118") (pintype "bidirectional"))
    )
    (net (code "214") (name "S34_P") (class "Default")
      (node (ref "SENSOR") (pin "C8") (pinfunction "OUT4_P_C8") (pintype "output"))
      (node (ref "X-SOUTH") (pin "116") (pinfunction "116_116") (pintype "bidirectional"))
    )
    (net (code "215") (name "S35_N") (class "Default")
      (node (ref "SENSOR") (pin "B6") (pinfunction "OUT1_N_B6") (pintype "output"))
      (node (ref "X-SOUTH") (pin "119") (pinfunction "119_119") (pintype "bidirectional"))
    )
    (net (code "216") (name "S35_P") (class "Default")
      (node (ref "SENSOR") (pin "B7") (pinfunction "OUT1_P_B7") (pintype "output"))
      (node (ref "X-SOUTH") (pin "117") (pinfunction "117_117") (pintype "bidirectional"))
    )
    (net (code "217") (name "S36_N") (class "Default")
      (node (ref "SENSOR") (pin "D7") (pinfunction "OUT3_N_D7") (pintype "output"))
      (node (ref "X-SOUTH") (pin "124") (pinfunction "124_124") (pintype "bidirectional"))
    )
    (net (code "218") (name "S36_P") (class "Default")
      (node (ref "SENSOR") (pin "D8") (pinfunction "OUT3_P_D8") (pintype "output"))
      (node (ref "X-SOUTH") (pin "122") (pinfunction "122_122") (pintype "bidirectional"))
    )
    (net (code "219") (name "S37_N") (class "Default")
      (node (ref "SENSOR") (pin "A5") (pinfunction "OUTCTR_N_A5") (pintype "output"))
      (node (ref "X-SOUTH") (pin "125") (pinfunction "125_125") (pintype "bidirectional"))
    )
    (net (code "220") (name "S37_P") (class "Default")
      (node (ref "SENSOR") (pin "A6") (pinfunction "OUTCTR_P_A6") (pintype "output"))
      (node (ref "X-SOUTH") (pin "123") (pinfunction "123_123") (pintype "bidirectional"))
    )
    (net (code "221") (name "S38_N") (class "Default")
      (node (ref "X-SOUTH") (pin "130") (pinfunction "130_130") (pintype "bidirectional"))
    )
    (net (code "222") (name "S38_P") (class "Default")
      (node (ref "X-SOUTH") (pin "128") (pinfunction "128_128") (pintype "bidirectional"))
    )
    (net (code "223") (name "S39_N") (class "Default")
      (node (ref "U3") (pin "6") (pinfunction "EN_6") (pintype "input"))
      (node (ref "X-SOUTH") (pin "131") (pinfunction "131_131") (pintype "bidirectional"))
    )
    (net (code "224") (name "S39_P") (class "Default")
      (node (ref "X-SOUTH") (pin "129") (pinfunction "129_129") (pintype "bidirectional"))
    )
    (net (code "225") (name "SPI_CLK") (class "Default")
      (node (ref "SENSOR") (pin "H29") (pinfunction "SPI_CLK_H29") (pintype "input"))
      (node (ref "U4") (pin "6") (pinfunction "1A1_6") (pintype "output"))
    )
    (net (code "226") (name "SPI_EN") (class "Default")
      (node (ref "SENSOR") (pin "F28") (pinfunction "SPI_EN_F28") (pintype "input"))
      (node (ref "U6") (pin "9") (pinfunction "B4_9") (pintype "bidirectional"))
    )
    (net (code "227") (name "SPI_IN") (class "Default")
      (node (ref "SENSOR") (pin "E28") (pinfunction "SPI_IN_E28") (pintype "input"))
      (node (ref "U4") (pin "7") (pinfunction "1A2_7") (pintype "output"))
    )
    (net (code "228") (name "SPI_OUT") (class "Default")
      (node (ref "SENSOR") (pin "G28") (pinfunction "SPI_OUT_G28") (pintype "output"))
      (node (ref "U4") (pin "8") (pinfunction "2A1_8") (pintype "output"))
    )
    (net (code "229") (name "SYS_RES_N") (class "Default")
      (node (ref "SENSOR") (pin "F30") (pinfunction "SYS_RES_N_F30") (pintype "input"))
      (node (ref "U5") (pin "10") (pinfunction "B3_10") (pintype "bidirectional"))
    )
    (net (code "230") (name "S_CHK_V") (class "Default")
      (node (ref "C5") (pin "1") (pinfunction "1_1") (pintype "passive"))
      (node (ref "C6") (pin "1") (pinfunction "1_1") (pintype "passive"))
      (node (ref "C7") (pin "1") (pinfunction "1_1") (pintype "passive"))
      (node (ref "R20") (pin "1") (pinfunction "1_1") (pintype "passive"))
      (node (ref "TP3") (pin "TP") (pinfunction "TP_TP") (pintype "input"))
      (node (ref "USE") (pin "8") (pinfunction "VDD_8") (pintype "power_in"))
      (node (ref "USS") (pin "8") (pinfunction "VDD_8") (pintype "power_in"))
      (node (ref "USW") (pin "8") (pinfunction "VDD_8") (pintype "power_in"))
      (node (ref "X-SOUTH") (pin "10") (pinfunction "10_10") (pintype "bidirectional"))
      (node (ref "X-SOUTH") (pin "8") (pinfunction "8_8") (pintype "bidirectional"))
    )
    (net (code "231") (name "S_I2C_V") (class "Default")
      (node (ref "X-SOUTH") (pin "135") (pinfunction "135_135") (pintype "bidirectional"))
      (node (ref "X-SOUTH") (pin "137") (pinfunction "137_137") (pintype "bidirectional"))
    )
    (net (code "232") (name "S_REF") (class "Default")
      (node (ref "R20") (pin "2") (pinfunction "2_2") (pintype "passive"))
      (node (ref "TP4") (pin "TP") (pinfunction "TP_TP") (pintype "input"))
      (node (ref "U2") (pin "1") (pinfunction "CATHODE_1") (pintype "output"))
      (node (ref "U2") (pin "3") (pinfunction "REF_3") (pintype "input"))
      (node (ref "USE") (pin "2") (pinfunction "VINA-_2") (pintype "input"))
      (node (ref "USE") (pin "5") (pinfunction "VINB+_5") (pintype "input"))
      (node (ref "USS") (pin "2") (pinfunction "VINA-_2") (pintype "input"))
      (node (ref "USS") (pin "5") (pinfunction "VINB+_5") (pintype "input"))
      (node (ref "USW") (pin "2") (pinfunction "VINA-_2") (pintype "input"))
      (node (ref "USW") (pin "5") (pinfunction "VINB+_5") (pintype "input"))
    )
    (net (code "233") (name "S_SCK") (class "Default")
      (node (ref "X-SOUTH") (pin "144") (pinfunction "144_144") (pintype "bidirectional"))
    )
    (net (code "234") (name "S_SCL") (class "Default")
      (node (ref "X-SOUTH") (pin "143") (pinfunction "143_143") (pintype "bidirectional"))
    )
    (net (code "235") (name "S_SDA") (class "Default")
      (node (ref "X-SOUTH") (pin "141") (pinfunction "141_141") (pintype "bidirectional"))
    )
    (net (code "236") (name "S_SDI") (class "Default")
      (node (ref "X-SOUTH") (pin "140") (pinfunction "140_140") (pintype "bidirectional"))
    )
    (net (code "237") (name "S_SDO") (class "Default")
      (node (ref "X-SOUTH") (pin "142") (pinfunction "142_142") (pintype "bidirectional"))
    )
    (net (code "238") (name "S_SPI_V") (class "Default")
      (node (ref "X-SOUTH") (pin "134") (pinfunction "134_134") (pintype "bidirectional"))
      (node (ref "X-SOUTH") (pin "136") (pinfunction "136_136") (pintype "bidirectional"))
    )
    (net (code "239") (name "S_VE") (class "Default")
      (node (ref "X-SOUTH") (pin "13") (pinfunction "13_13") (pintype "bidirectional"))
      (node (ref "X-SOUTH") (pin "19") (pinfunction "19_19") (pintype "bidirectional"))
      (node (ref "X-SOUTH") (pin "25") (pinfunction "25_25") (pintype "bidirectional"))
      (node (ref "X-SOUTH") (pin "31") (pinfunction "31_31") (pintype "bidirectional"))
      (node (ref "X-SOUTH") (pin "37") (pinfunction "37_37") (pintype "bidirectional"))
    )
    (net (code "240") (name "S_VE_CV") (class "Default")
      (node (ref "C11") (pin "1") (pinfunction "1_1") (pintype "passive"))
      (node (ref "R10") (pin "1") (pinfunction "1_1") (pintype "passive"))
      (node (ref "X-SOUTH") (pin "2") (pinfunction "2_2") (pintype "bidirectional"))
    )
    (net (code "241") (name "S_VE_OV") (class "Default")
      (node (ref "USE") (pin "7") (pinfunction "OUTB_7") (pintype "output"))
      (node (ref "X-SOUTH") (pin "1") (pinfunction "1_1") (pintype "bidirectional"))
    )
    (net (code "242") (name "S_VE_UV") (class "Default")
      (node (ref "USE") (pin "1") (pinfunction "OUTA_1") (pintype "output"))
      (node (ref "X-SOUTH") (pin "7") (pinfunction "7_7") (pintype "bidirectional"))
    )
    (net (code "243") (name "S_VS") (class "Default")
      (node (ref "C45") (pin "1") (pinfunction "1_1") (pintype "passive"))
      (node (ref "C46") (pin "1") (pinfunction "1_1") (pintype "passive"))
      (node (ref "C47") (pin "1") (pinfunction "1_1") (pintype "passive"))
      (node (ref "C48") (pin "1") (pinfunction "1_1") (pintype "passive"))
      (node (ref "C49") (pin "1") (pinfunction "1_1") (pintype "passive"))
      (node (ref "C72") (pin "1") (pinfunction "1_1") (pintype "passive"))
      (node (ref "C73") (pin "1") (pinfunction "1_1") (pintype "passive"))
      (node (ref "C74") (pin "1") (pinfunction "1_1") (pintype "passive"))
      (node (ref "C81") (pin "1") (pinfunction "1_1") (pintype "passive"))
      (node (ref "C82") (pin "1") (pinfunction "1_1") (pintype "passive"))
      (node (ref "C83") (pin "1") (pinfunction "1_1") (pintype "passive"))
      (node (ref "SENSOR") (pin "A30") (pinfunction "VDD_PIX_A30") (pintype "power_in"))
      (node (ref "SENSOR") (pin "D28") (pinfunction "VDD_PIX_D28") (pintype "power_in"))
      (node (ref "SENSOR") (pin "D30") (pinfunction "VDD_PIX_D30") (pintype "power_in"))
      (node (ref "SENSOR") (pin "G1") (pinfunction "VDD_PIX_G1") (pintype "power_in"))
      (node (ref "SENSOR") (pin "H28") (pinfunction "VDD_PIX_H28") (pintype "power_in"))
      (node (ref "TP6") (pin "TP") (pinfunction "TP_TP") (pintype "input"))
      (node (ref "X-SOUTH") (pin "49") (pinfunction "49_49") (pintype "bidirectional"))
      (node (ref "X-SOUTH") (pin "55") (pinfunction "55_55") (pintype "bidirectional"))
      (node (ref "X-SOUTH") (pin "61") (pinfunction "61_61") (pintype "bidirectional"))
      (node (ref "X-SOUTH") (pin "67") (pinfunction "67_67") (pintype "bidirectional"))
      (node (ref "X-SOUTH") (pin "73") (pinfunction "73_73") (pintype "bidirectional"))
      (node (ref "X-SOUTH") (pin "79") (pinfunction "79_79") (pintype "bidirectional"))
      (node (ref "X-SOUTH") (pin "85") (pinfunction "85_85") (pintype "bidirectional"))
      (node (ref "X-SOUTH") (pin "91") (pinfunction "91_91") (pintype "bidirectional"))
      (node (ref "X-SOUTH") (pin "97") (pinfunction "97_97") (pintype "bidirectional"))
    )
    (net (code "244") (name "S_VS_CV") (class "Default")
      (node (ref "C12") (pin "1") (pinfunction "1_1") (pintype "passive"))
      (node (ref "R13") (pin "1") (pinfunction "1_1") (pintype "passive"))
      (node (ref "X-SOUTH") (pin "4") (pinfunction "4_4") (pintype "bidirectional"))
    )
    (net (code "245") (name "S_VS_OV") (class "Default")
      (node (ref "USS") (pin "7") (pinfunction "OUTB_7") (pintype "output"))
      (node (ref "X-SOUTH") (pin "3") (pinfunction "3_3") (pintype "bidirectional"))
    )
    (net (code "246") (name "S_VS_UV") (class "Default")
      (node (ref "USS") (pin "1") (pinfunction "OUTA_1") (pintype "output"))
      (node (ref "X-SOUTH") (pin "9") (pinfunction "9_9") (pintype "bidirectional"))
    )
    (net (code "247") (name "S_VW") (class "Default")
      (node (ref "C90") (pin "1") (pinfunction "1_1") (pintype "passive"))
      (node (ref "U3") (pin "1") (pinfunction "BIAS_1") (pintype "power_in"))
      (node (ref "U3") (pin "3") (pinfunction "IN_3") (pintype "power_in"))
      (node (ref "X-SOUTH") (pin "109") (pinfunction "109_109") (pintype "bidirectional"))
      (node (ref "X-SOUTH") (pin "115") (pinfunction "115_115") (pintype "bidirectional"))
      (node (ref "X-SOUTH") (pin "121") (pinfunction "121_121") (pintype "bidirectional"))
      (node (ref "X-SOUTH") (pin "127") (pinfunction "127_127") (pintype "bidirectional"))
      (node (ref "X-SOUTH") (pin "133") (pinfunction "133_133") (pintype "bidirectional"))
    )
    (net (code "248") (name "S_VW_CV") (class "Default")
      (node (ref "C13") (pin "1") (pinfunction "1_1") (pintype "passive"))
      (node (ref "R16") (pin "1") (pinfunction "1_1") (pintype "passive"))
      (node (ref "X-SOUTH") (pin "6") (pinfunction "6_6") (pintype "bidirectional"))
    )
    (net (code "249") (name "S_VW_OV") (class "Default")
      (node (ref "USW") (pin "7") (pinfunction "OUTB_7") (pintype "output"))
      (node (ref "X-SOUTH") (pin "5") (pinfunction "5_5") (pintype "bidirectional"))
    )
    (net (code "250") (name "S_VW_UV") (class "Default")
      (node (ref "USW") (pin "1") (pinfunction "OUTA_1") (pintype "output"))
      (node (ref "X-SOUTH") (pin "11") (pinfunction "11_11") (pintype "bidirectional"))
    )
    (net (code "251") (name "TDIG1") (class "Default")
      (node (ref "SENSOR") (pin "G27") (pinfunction "TDIG1_G27") (pintype "output"))
      (node (ref "U5") (pin "9") (pinfunction "B4_9") (pintype "bidirectional"))
    )
    (net (code "252") (name "TDIG2") (class "Default")
      (node (ref "SENSOR") (pin "G26") (pinfunction "TDIG2_G26") (pintype "output"))
      (node (ref "U6") (pin "11") (pinfunction "B2_11") (pintype "bidirectional"))
    )
    (net (code "253") (name "T_EXP1") (class "Default")
      (node (ref "SENSOR") (pin "H30") (pinfunction "T_EXP1_H30") (pintype "input"))
      (node (ref "U5") (pin "12") (pinfunction "B1_12") (pintype "bidirectional"))
    )
    (net (code "254") (name "T_EXP2") (class "Default")
      (node (ref "SENSOR") (pin "E29") (pinfunction "T_EXP2_E29") (pintype "input"))
      (node (ref "U6") (pin "10") (pinfunction "B3_10") (pintype "bidirectional"))
    )
    (net (code "255") (name "VRAMP1") (class "Default")
      (node (ref "C16") (pin "1") (pinfunction "1_1") (pintype "passive"))
      (node (ref "R23") (pin "1") (pinfunction "1_1") (pintype "passive"))
      (node (ref "SENSOR") (pin "G29") (pinfunction "VRAMP1_G29") (pintype "bidirectional"))
    )
    (net (code "256") (name "VRAMP2") (class "Default")
      (node (ref "C17") (pin "1") (pinfunction "1_1") (pintype "passive"))
      (node (ref "R23") (pin "2") (pinfunction "2_2") (pintype "passive"))
      (node (ref "SENSOR") (pin "F29") (pinfunction "VRAMP2_F29") (pintype "bidirectional"))
    )
    (net (code "257") (name "VTREF") (class "Default")
      (node (ref "C65") (pin "1") (pinfunction "1_1") (pintype "passive"))
      (node (ref "C91") (pin "2") (pinfunction "2_2") (pintype "passive"))
      (node (ref "R21") (pin "2") (pinfunction "2_2") (pintype "passive"))
      (node (ref "R24") (pin "1") (pinfunction "1_1") (pintype "passive"))
      (node (ref "SENSOR") (pin "B2") (pinfunction "VTREF_B2") (pintype "bidirectional"))
      (node (ref "U3") (pin "4") (pinfunction "OUT_4") (pintype "power_in"))
    )
    (net (code "258") (name "VTSIG") (class "Default")
      (node (ref "C66") (pin "1") (pinfunction "1_1") (pintype "passive"))
      (node (ref "R24") (pin "2") (pinfunction "2_2") (pintype "passive"))
      (node (ref "SENSOR") (pin "C2") (pinfunction "VTSIG_C2") (pintype "bidirectional"))
    )
    (net (code "259") (name "unconnected-(U1-NC-Pad2)") (class "Default")
      (node (ref "U1") (pin "2") (pinfunction "NC_2") (pintype "no_connect"))
    )
    (net (code "260") (name "unconnected-(U1-NC-Pad4)") (class "Default")
      (node (ref "U1") (pin "4") (pinfunction "NC_4") (pintype "no_connect"))
    )
    (net (code "261") (name "unconnected-(U1-NC-Pad5)") (class "Default")
      (node (ref "U1") (pin "5") (pinfunction "NC_5") (pintype "no_connect"))
    )
    (net (code "262") (name "unconnected-(U2-NC-Pad2)") (class "Default")
      (node (ref "U2") (pin "2") (pinfunction "NC_2") (pintype "no_connect"))
    )
    (net (code "263") (name "unconnected-(U2-NC-Pad4)") (class "Default")
      (node (ref "U2") (pin "4") (pinfunction "NC_4") (pintype "no_connect"))
    )
    (net (code "264") (name "unconnected-(U2-NC-Pad5)") (class "Default")
      (node (ref "U2") (pin "5") (pinfunction "NC_5") (pintype "no_connect"))
    )
    (net (code "265") (name "unconnected-(U4-2B2-Pad12)") (class "Default")
      (node (ref "U4") (pin "12") (pinfunction "2B2_12") (pintype "output"))
    )
    (net (code "266") (name "unconnected-(X-NORTH-PadM1)") (class "Default")
      (node (ref "X-NORTH") (pin "M1") (pinfunction "M1_M1") (pintype "bidirectional"))
    )
    (net (code "267") (name "unconnected-(X-NORTH-PadM2)") (class "Default")
      (node (ref "X-NORTH") (pin "M2") (pinfunction "M2_M2") (pintype "bidirectional"))
    )
    (net (code "268") (name "unconnected-(X-SOUTH-PadM1)") (class "Default")
      (node (ref "X-SOUTH") (pin "M1") (pinfunction "M1_M1") (pintype "bidirectional"))
    )
    (net (code "269") (name "unconnected-(X-SOUTH-PadM2)") (class "Default")
      (node (ref "X-SOUTH") (pin "M2") (pinfunction "M2_M2") (pintype "bidirectional"))
    )
  )
)
